# main_board.net
KiCad netlist of a schematic drawn in EAGLE
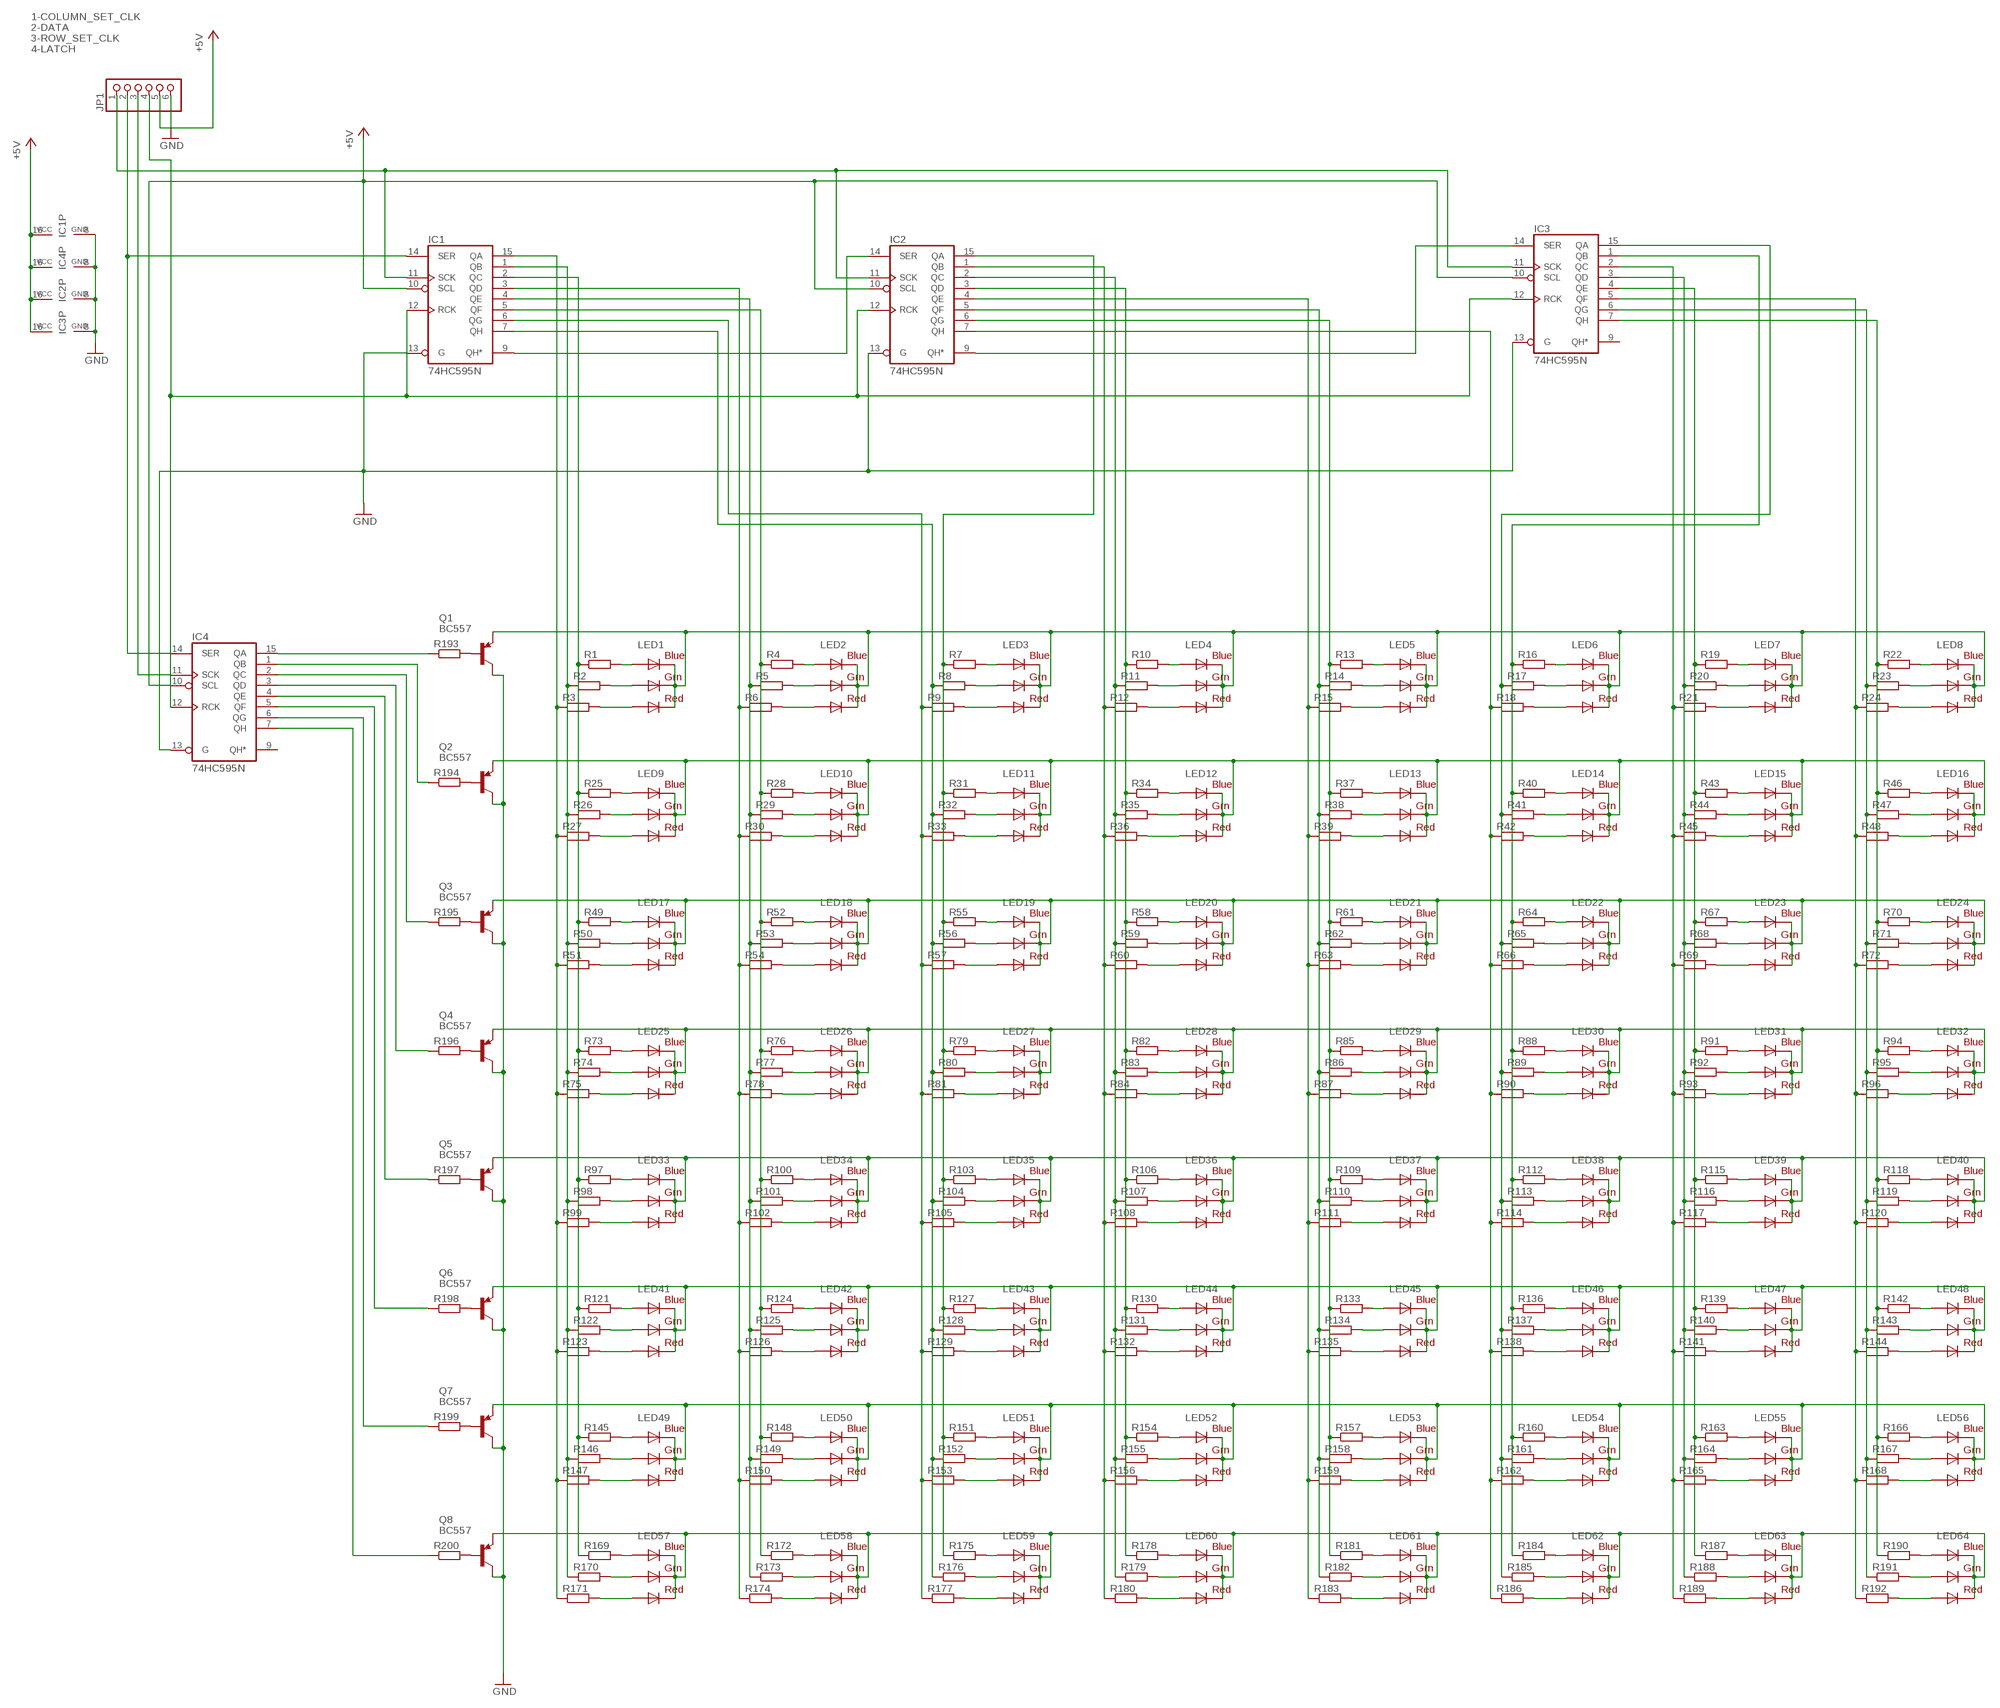
[diagram p0: schematic, sheet 1]

(export (version "E")
  (design (tool "Eeschema 10.0.6"))
  (components
    (comp (ref "IC1")
      (value "74HC595N")
      (footprint "eagle-import:DIL16")
      (libsource (lib "eagle-import") (part "74595NHC"))
    )
    (comp (ref "IC2")
      (value "74HC595N")
      (footprint "eagle-import:DIL16")
      (libsource (lib "eagle-import") (part "74595NHC"))
    )
    (comp (ref "IC3")
      (value "74HC595N")
      (footprint "eagle-import:DIL16")
      (libsource (lib "eagle-import") (part "74595NHC"))
    )
    (comp (ref "IC4")
      (value "74HC595N")
      (footprint "eagle-import:DIL16")
      (libsource (lib "eagle-import") (part "74595NHC"))
    )
    (comp (ref "JP1")
      (value "PINHD-1X6")
      (footprint "eagle-import:1X06")
      (libsource (lib "eagle-import") (part "PINHD-1X6"))
    )
    (comp (ref "LED1")
      (value "RGBLED5050")
      (footprint "eagle-import:RGBLED5050")
      (libsource (lib "eagle-import") (part "RGBLED5050"))
    )
    (comp (ref "LED2")
      (value "RGBLED5050")
      (footprint "eagle-import:RGBLED5050")
      (libsource (lib "eagle-import") (part "RGBLED5050"))
    )
    (comp (ref "LED3")
      (value "RGBLED5050")
      (footprint "eagle-import:RGBLED5050")
      (libsource (lib "eagle-import") (part "RGBLED5050"))
    )
    (comp (ref "LED4")
      (value "RGBLED5050")
      (footprint "eagle-import:RGBLED5050")
      (libsource (lib "eagle-import") (part "RGBLED5050"))
    )
    (comp (ref "LED5")
      (value "RGBLED5050")
      (footprint "eagle-import:RGBLED5050")
      (libsource (lib "eagle-import") (part "RGBLED5050"))
    )
    (comp (ref "LED6")
      (value "RGBLED5050")
      (footprint "eagle-import:RGBLED5050")
      (libsource (lib "eagle-import") (part "RGBLED5050"))
    )
    (comp (ref "LED7")
      (value "RGBLED5050")
      (footprint "eagle-import:RGBLED5050")
      (libsource (lib "eagle-import") (part "RGBLED5050"))
    )
    (comp (ref "LED8")
      (value "RGBLED5050")
      (footprint "eagle-import:RGBLED5050")
      (libsource (lib "eagle-import") (part "RGBLED5050"))
    )
    (comp (ref "LED9")
      (value "RGBLED5050")
      (footprint "eagle-import:RGBLED5050")
      (libsource (lib "eagle-import") (part "RGBLED5050"))
    )
    (comp (ref "LED10")
      (value "RGBLED5050")
      (footprint "eagle-import:RGBLED5050")
      (libsource (lib "eagle-import") (part "RGBLED5050"))
    )
    (comp (ref "LED11")
      (value "RGBLED5050")
      (footprint "eagle-import:RGBLED5050")
      (libsource (lib "eagle-import") (part "RGBLED5050"))
    )
    (comp (ref "LED12")
      (value "RGBLED5050")
      (footprint "eagle-import:RGBLED5050")
      (libsource (lib "eagle-import") (part "RGBLED5050"))
    )
    (comp (ref "LED13")
      (value "RGBLED5050")
      (footprint "eagle-import:RGBLED5050")
      (libsource (lib "eagle-import") (part "RGBLED5050"))
    )
    (comp (ref "LED14")
      (value "RGBLED5050")
      (footprint "eagle-import:RGBLED5050")
      (libsource (lib "eagle-import") (part "RGBLED5050"))
    )
    (comp (ref "LED15")
      (value "RGBLED5050")
      (footprint "eagle-import:RGBLED5050")
      (libsource (lib "eagle-import") (part "RGBLED5050"))
    )
    (comp (ref "LED16")
      (value "RGBLED5050")
      (footprint "eagle-import:RGBLED5050")
      (libsource (lib "eagle-import") (part "RGBLED5050"))
    )
    (comp (ref "LED17")
      (value "RGBLED5050")
      (footprint "eagle-import:RGBLED5050")
      (libsource (lib "eagle-import") (part "RGBLED5050"))
    )
    (comp (ref "LED18")
      (value "RGBLED5050")
      (footprint "eagle-import:RGBLED5050")
      (libsource (lib "eagle-import") (part "RGBLED5050"))
    )
    (comp (ref "LED19")
      (value "RGBLED5050")
      (footprint "eagle-import:RGBLED5050")
      (libsource (lib "eagle-import") (part "RGBLED5050"))
    )
    (comp (ref "LED20")
      (value "RGBLED5050")
      (footprint "eagle-import:RGBLED5050")
      (libsource (lib "eagle-import") (part "RGBLED5050"))
    )
    (comp (ref "LED21")
      (value "RGBLED5050")
      (footprint "eagle-import:RGBLED5050")
      (libsource (lib "eagle-import") (part "RGBLED5050"))
    )
    (comp (ref "LED22")
      (value "RGBLED5050")
      (footprint "eagle-import:RGBLED5050")
      (libsource (lib "eagle-import") (part "RGBLED5050"))
    )
    (comp (ref "LED23")
      (value "RGBLED5050")
      (footprint "eagle-import:RGBLED5050")
      (libsource (lib "eagle-import") (part "RGBLED5050"))
    )
    (comp (ref "LED24")
      (value "RGBLED5050")
      (footprint "eagle-import:RGBLED5050")
      (libsource (lib "eagle-import") (part "RGBLED5050"))
    )
    (comp (ref "LED25")
      (value "RGBLED5050")
      (footprint "eagle-import:RGBLED5050")
      (libsource (lib "eagle-import") (part "RGBLED5050"))
    )
    (comp (ref "LED26")
      (value "RGBLED5050")
      (footprint "eagle-import:RGBLED5050")
      (libsource (lib "eagle-import") (part "RGBLED5050"))
    )
    (comp (ref "LED27")
      (value "RGBLED5050")
      (footprint "eagle-import:RGBLED5050")
      (libsource (lib "eagle-import") (part "RGBLED5050"))
    )
    (comp (ref "LED28")
      (value "RGBLED5050")
      (footprint "eagle-import:RGBLED5050")
      (libsource (lib "eagle-import") (part "RGBLED5050"))
    )
    (comp (ref "LED29")
      (value "RGBLED5050")
      (footprint "eagle-import:RGBLED5050")
      (libsource (lib "eagle-import") (part "RGBLED5050"))
    )
    (comp (ref "LED30")
      (value "RGBLED5050")
      (footprint "eagle-import:RGBLED5050")
      (libsource (lib "eagle-import") (part "RGBLED5050"))
    )
    (comp (ref "LED31")
      (value "RGBLED5050")
      (footprint "eagle-import:RGBLED5050")
      (libsource (lib "eagle-import") (part "RGBLED5050"))
    )
    (comp (ref "LED32")
      (value "RGBLED5050")
      (footprint "eagle-import:RGBLED5050")
      (libsource (lib "eagle-import") (part "RGBLED5050"))
    )
    (comp (ref "LED33")
      (value "RGBLED5050")
      (footprint "eagle-import:RGBLED5050")
      (libsource (lib "eagle-import") (part "RGBLED5050"))
    )
    (comp (ref "LED34")
      (value "RGBLED5050")
      (footprint "eagle-import:RGBLED5050")
      (libsource (lib "eagle-import") (part "RGBLED5050"))
    )
    (comp (ref "LED35")
      (value "RGBLED5050")
      (footprint "eagle-import:RGBLED5050")
      (libsource (lib "eagle-import") (part "RGBLED5050"))
    )
    (comp (ref "LED36")
      (value "RGBLED5050")
      (footprint "eagle-import:RGBLED5050")
      (libsource (lib "eagle-import") (part "RGBLED5050"))
    )
    (comp (ref "LED37")
      (value "RGBLED5050")
      (footprint "eagle-import:RGBLED5050")
      (libsource (lib "eagle-import") (part "RGBLED5050"))
    )
    (comp (ref "LED38")
      (value "RGBLED5050")
      (footprint "eagle-import:RGBLED5050")
      (libsource (lib "eagle-import") (part "RGBLED5050"))
    )
    (comp (ref "LED39")
      (value "RGBLED5050")
      (footprint "eagle-import:RGBLED5050")
      (libsource (lib "eagle-import") (part "RGBLED5050"))
    )
    (comp (ref "LED40")
      (value "RGBLED5050")
      (footprint "eagle-import:RGBLED5050")
      (libsource (lib "eagle-import") (part "RGBLED5050"))
    )
    (comp (ref "LED41")
      (value "RGBLED5050")
      (footprint "eagle-import:RGBLED5050")
      (libsource (lib "eagle-import") (part "RGBLED5050"))
    )
    (comp (ref "LED42")
      (value "RGBLED5050")
      (footprint "eagle-import:RGBLED5050")
      (libsource (lib "eagle-import") (part "RGBLED5050"))
    )
    (comp (ref "LED43")
      (value "RGBLED5050")
      (footprint "eagle-import:RGBLED5050")
      (libsource (lib "eagle-import") (part "RGBLED5050"))
    )
    (comp (ref "LED44")
      (value "RGBLED5050")
      (footprint "eagle-import:RGBLED5050")
      (libsource (lib "eagle-import") (part "RGBLED5050"))
    )
    (comp (ref "LED45")
      (value "RGBLED5050")
      (footprint "eagle-import:RGBLED5050")
      (libsource (lib "eagle-import") (part "RGBLED5050"))
    )
    (comp (ref "LED46")
      (value "RGBLED5050")
      (footprint "eagle-import:RGBLED5050")
      (libsource (lib "eagle-import") (part "RGBLED5050"))
    )
    (comp (ref "LED47")
      (value "RGBLED5050")
      (footprint "eagle-import:RGBLED5050")
      (libsource (lib "eagle-import") (part "RGBLED5050"))
    )
    (comp (ref "LED48")
      (value "RGBLED5050")
      (footprint "eagle-import:RGBLED5050")
      (libsource (lib "eagle-import") (part "RGBLED5050"))
    )
    (comp (ref "LED49")
      (value "RGBLED5050")
      (footprint "eagle-import:RGBLED5050")
      (libsource (lib "eagle-import") (part "RGBLED5050"))
    )
    (comp (ref "LED50")
      (value "RGBLED5050")
      (footprint "eagle-import:RGBLED5050")
      (libsource (lib "eagle-import") (part "RGBLED5050"))
    )
    (comp (ref "LED51")
      (value "RGBLED5050")
      (footprint "eagle-import:RGBLED5050")
      (libsource (lib "eagle-import") (part "RGBLED5050"))
    )
    (comp (ref "LED52")
      (value "RGBLED5050")
      (footprint "eagle-import:RGBLED5050")
      (libsource (lib "eagle-import") (part "RGBLED5050"))
    )
    (comp (ref "LED53")
      (value "RGBLED5050")
      (footprint "eagle-import:RGBLED5050")
      (libsource (lib "eagle-import") (part "RGBLED5050"))
    )
    (comp (ref "LED54")
      (value "RGBLED5050")
      (footprint "eagle-import:RGBLED5050")
      (libsource (lib "eagle-import") (part "RGBLED5050"))
    )
    (comp (ref "LED55")
      (value "RGBLED5050")
      (footprint "eagle-import:RGBLED5050")
      (libsource (lib "eagle-import") (part "RGBLED5050"))
    )
    (comp (ref "LED56")
      (value "RGBLED5050")
      (footprint "eagle-import:RGBLED5050")
      (libsource (lib "eagle-import") (part "RGBLED5050"))
    )
    (comp (ref "LED57")
      (value "RGBLED5050")
      (footprint "eagle-import:RGBLED5050")
      (libsource (lib "eagle-import") (part "RGBLED5050"))
    )
    (comp (ref "LED58")
      (value "RGBLED5050")
      (footprint "eagle-import:RGBLED5050")
      (libsource (lib "eagle-import") (part "RGBLED5050"))
    )
    (comp (ref "LED59")
      (value "RGBLED5050")
      (footprint "eagle-import:RGBLED5050")
      (libsource (lib "eagle-import") (part "RGBLED5050"))
    )
    (comp (ref "LED60")
      (value "RGBLED5050")
      (footprint "eagle-import:RGBLED5050")
      (libsource (lib "eagle-import") (part "RGBLED5050"))
    )
    (comp (ref "LED61")
      (value "RGBLED5050")
      (footprint "eagle-import:RGBLED5050")
      (libsource (lib "eagle-import") (part "RGBLED5050"))
    )
    (comp (ref "LED62")
      (value "RGBLED5050")
      (footprint "eagle-import:RGBLED5050")
      (libsource (lib "eagle-import") (part "RGBLED5050"))
    )
    (comp (ref "LED63")
      (value "RGBLED5050")
      (footprint "eagle-import:RGBLED5050")
      (libsource (lib "eagle-import") (part "RGBLED5050"))
    )
    (comp (ref "LED64")
      (value "RGBLED5050")
      (footprint "eagle-import:RGBLED5050")
      (libsource (lib "eagle-import") (part "RGBLED5050"))
    )
    (comp (ref "Q1")
      (value "BC557")
      (footprint "eagle-import:TO92")
      (libsource (lib "eagle-import") (part "BC557"))
    )
    (comp (ref "Q2")
      (value "BC557")
      (footprint "eagle-import:TO92")
      (libsource (lib "eagle-import") (part "BC557"))
    )
    (comp (ref "Q3")
      (value "BC557")
      (footprint "eagle-import:TO92")
      (libsource (lib "eagle-import") (part "BC557"))
    )
    (comp (ref "Q4")
      (value "BC557")
      (footprint "eagle-import:TO92")
      (libsource (lib "eagle-import") (part "BC557"))
    )
    (comp (ref "Q5")
      (value "BC557")
      (footprint "eagle-import:TO92")
      (libsource (lib "eagle-import") (part "BC557"))
    )
    (comp (ref "Q6")
      (value "BC557")
      (footprint "eagle-import:TO92")
      (libsource (lib "eagle-import") (part "BC557"))
    )
    (comp (ref "Q7")
      (value "BC557")
      (footprint "eagle-import:TO92")
      (libsource (lib "eagle-import") (part "BC557"))
    )
    (comp (ref "Q8")
      (value "BC557")
      (footprint "eagle-import:TO92")
      (libsource (lib "eagle-import") (part "BC557"))
    )
    (comp (ref "R1")
      (value "R-EU_R0805")
      (footprint "eagle-import:R0805")
      (libsource (lib "eagle-import") (part "R-EU_R0805"))
    )
    (comp (ref "R2")
      (value "R-EU_R0805")
      (footprint "eagle-import:R0805")
      (libsource (lib "eagle-import") (part "R-EU_R0805"))
    )
    (comp (ref "R3")
      (value "R-EU_R0805")
      (footprint "eagle-import:R0805")
      (libsource (lib "eagle-import") (part "R-EU_R0805"))
    )
    (comp (ref "R4")
      (value "R-EU_R0805")
      (footprint "eagle-import:R0805")
      (libsource (lib "eagle-import") (part "R-EU_R0805"))
    )
    (comp (ref "R5")
      (value "R-EU_R0805")
      (footprint "eagle-import:R0805")
      (libsource (lib "eagle-import") (part "R-EU_R0805"))
    )
    (comp (ref "R6")
      (value "R-EU_R0805")
      (footprint "eagle-import:R0805")
      (libsource (lib "eagle-import") (part "R-EU_R0805"))
    )
    (comp (ref "R7")
      (value "R-EU_R0805")
      (footprint "eagle-import:R0805")
      (libsource (lib "eagle-import") (part "R-EU_R0805"))
    )
    (comp (ref "R8")
      (value "R-EU_R0805")
      (footprint "eagle-import:R0805")
      (libsource (lib "eagle-import") (part "R-EU_R0805"))
    )
    (comp (ref "R9")
      (value "R-EU_R0805")
      (footprint "eagle-import:R0805")
      (libsource (lib "eagle-import") (part "R-EU_R0805"))
    )
    (comp (ref "R10")
      (value "R-EU_R0805")
      (footprint "eagle-import:R0805")
      (libsource (lib "eagle-import") (part "R-EU_R0805"))
    )
    (comp (ref "R11")
      (value "R-EU_R0805")
      (footprint "eagle-import:R0805")
      (libsource (lib "eagle-import") (part "R-EU_R0805"))
    )
    (comp (ref "R12")
      (value "R-EU_R0805")
      (footprint "eagle-import:R0805")
      (libsource (lib "eagle-import") (part "R-EU_R0805"))
    )
    (comp (ref "R13")
      (value "R-EU_R0805")
      (footprint "eagle-import:R0805")
      (libsource (lib "eagle-import") (part "R-EU_R0805"))
    )
    (comp (ref "R14")
      (value "R-EU_R0805")
      (footprint "eagle-import:R0805")
      (libsource (lib "eagle-import") (part "R-EU_R0805"))
    )
    (comp (ref "R15")
      (value "R-EU_R0805")
      (footprint "eagle-import:R0805")
      (libsource (lib "eagle-import") (part "R-EU_R0805"))
    )
    (comp (ref "R16")
      (value "R-EU_R0805")
      (footprint "eagle-import:R0805")
      (libsource (lib "eagle-import") (part "R-EU_R0805"))
    )
    (comp (ref "R17")
      (value "R-EU_R0805")
      (footprint "eagle-import:R0805")
      (libsource (lib "eagle-import") (part "R-EU_R0805"))
    )
    (comp (ref "R18")
      (value "R-EU_R0805")
      (footprint "eagle-import:R0805")
      (libsource (lib "eagle-import") (part "R-EU_R0805"))
    )
    (comp (ref "R19")
      (value "R-EU_R0805")
      (footprint "eagle-import:R0805")
      (libsource (lib "eagle-import") (part "R-EU_R0805"))
    )
    (comp (ref "R20")
      (value "R-EU_R0805")
      (footprint "eagle-import:R0805")
      (libsource (lib "eagle-import") (part "R-EU_R0805"))
    )
    (comp (ref "R21")
      (value "R-EU_R0805")
      (footprint "eagle-import:R0805")
      (libsource (lib "eagle-import") (part "R-EU_R0805"))
    )
    (comp (ref "R22")
      (value "R-EU_R0805")
      (footprint "eagle-import:R0805")
      (libsource (lib "eagle-import") (part "R-EU_R0805"))
    )
    (comp (ref "R23")
      (value "R-EU_R0805")
      (footprint "eagle-import:R0805")
      (libsource (lib "eagle-import") (part "R-EU_R0805"))
    )
    (comp (ref "R24")
      (value "R-EU_R0805")
      (footprint "eagle-import:R0805")
      (libsource (lib "eagle-import") (part "R-EU_R0805"))
    )
    (comp (ref "R25")
      (value "R-EU_R0805")
      (footprint "eagle-import:R0805")
      (libsource (lib "eagle-import") (part "R-EU_R0805"))
    )
    (comp (ref "R26")
      (value "R-EU_R0805")
      (footprint "eagle-import:R0805")
      (libsource (lib "eagle-import") (part "R-EU_R0805"))
    )
    (comp (ref "R27")
      (value "R-EU_R0805")
      (footprint "eagle-import:R0805")
      (libsource (lib "eagle-import") (part "R-EU_R0805"))
    )
    (comp (ref "R28")
      (value "R-EU_R0805")
      (footprint "eagle-import:R0805")
      (libsource (lib "eagle-import") (part "R-EU_R0805"))
    )
    (comp (ref "R29")
      (value "R-EU_R0805")
      (footprint "eagle-import:R0805")
      (libsource (lib "eagle-import") (part "R-EU_R0805"))
    )
    (comp (ref "R30")
      (value "R-EU_R0805")
      (footprint "eagle-import:R0805")
      (libsource (lib "eagle-import") (part "R-EU_R0805"))
    )
    (comp (ref "R31")
      (value "R-EU_R0805")
      (footprint "eagle-import:R0805")
      (libsource (lib "eagle-import") (part "R-EU_R0805"))
    )
    (comp (ref "R32")
      (value "R-EU_R0805")
      (footprint "eagle-import:R0805")
      (libsource (lib "eagle-import") (part "R-EU_R0805"))
    )
    (comp (ref "R33")
      (value "R-EU_R0805")
      (footprint "eagle-import:R0805")
      (libsource (lib "eagle-import") (part "R-EU_R0805"))
    )
    (comp (ref "R34")
      (value "R-EU_R0805")
      (footprint "eagle-import:R0805")
      (libsource (lib "eagle-import") (part "R-EU_R0805"))
    )
    (comp (ref "R35")
      (value "R-EU_R0805")
      (footprint "eagle-import:R0805")
      (libsource (lib "eagle-import") (part "R-EU_R0805"))
    )
    (comp (ref "R36")
      (value "R-EU_R0805")
      (footprint "eagle-import:R0805")
      (libsource (lib "eagle-import") (part "R-EU_R0805"))
    )
    (comp (ref "R37")
      (value "R-EU_R0805")
      (footprint "eagle-import:R0805")
      (libsource (lib "eagle-import") (part "R-EU_R0805"))
    )
    (comp (ref "R38")
      (value "R-EU_R0805")
      (footprint "eagle-import:R0805")
      (libsource (lib "eagle-import") (part "R-EU_R0805"))
    )
    (comp (ref "R39")
      (value "R-EU_R0805")
      (footprint "eagle-import:R0805")
      (libsource (lib "eagle-import") (part "R-EU_R0805"))
    )
    (comp (ref "R40")
      (value "R-EU_R0805")
      (footprint "eagle-import:R0805")
      (libsource (lib "eagle-import") (part "R-EU_R0805"))
    )
    (comp (ref "R41")
      (value "R-EU_R0805")
      (footprint "eagle-import:R0805")
      (libsource (lib "eagle-import") (part "R-EU_R0805"))
    )
    (comp (ref "R42")
      (value "R-EU_R0805")
      (footprint "eagle-import:R0805")
      (libsource (lib "eagle-import") (part "R-EU_R0805"))
    )
    (comp (ref "R43")
      (value "R-EU_R0805")
      (footprint "eagle-import:R0805")
      (libsource (lib "eagle-import") (part "R-EU_R0805"))
    )
    (comp (ref "R44")
      (value "R-EU_R0805")
      (footprint "eagle-import:R0805")
      (libsource (lib "eagle-import") (part "R-EU_R0805"))
    )
    (comp (ref "R45")
      (value "R-EU_R0805")
      (footprint "eagle-import:R0805")
      (libsource (lib "eagle-import") (part "R-EU_R0805"))
    )
    (comp (ref "R46")
      (value "R-EU_R0805")
      (footprint "eagle-import:R0805")
      (libsource (lib "eagle-import") (part "R-EU_R0805"))
    )
    (comp (ref "R47")
      (value "R-EU_R0805")
      (footprint "eagle-import:R0805")
      (libsource (lib "eagle-import") (part "R-EU_R0805"))
    )
    (comp (ref "R48")
      (value "R-EU_R0805")
      (footprint "eagle-import:R0805")
      (libsource (lib "eagle-import") (part "R-EU_R0805"))
    )
    (comp (ref "R49")
      (value "R-EU_R0805")
      (footprint "eagle-import:R0805")
      (libsource (lib "eagle-import") (part "R-EU_R0805"))
    )
    (comp (ref "R50")
      (value "R-EU_R0805")
      (footprint "eagle-import:R0805")
      (libsource (lib "eagle-import") (part "R-EU_R0805"))
    )
    (comp (ref "R51")
      (value "R-EU_R0805")
      (footprint "eagle-import:R0805")
      (libsource (lib "eagle-import") (part "R-EU_R0805"))
    )
    (comp (ref "R52")
      (value "R-EU_R0805")
      (footprint "eagle-import:R0805")
      (libsource (lib "eagle-import") (part "R-EU_R0805"))
    )
    (comp (ref "R53")
      (value "R-EU_R0805")
      (footprint "eagle-import:R0805")
      (libsource (lib "eagle-import") (part "R-EU_R0805"))
    )
    (comp (ref "R54")
      (value "R-EU_R0805")
      (footprint "eagle-import:R0805")
      (libsource (lib "eagle-import") (part "R-EU_R0805"))
    )
    (comp (ref "R55")
      (value "R-EU_R0805")
      (footprint "eagle-import:R0805")
      (libsource (lib "eagle-import") (part "R-EU_R0805"))
    )
    (comp (ref "R56")
      (value "R-EU_R0805")
      (footprint "eagle-import:R0805")
      (libsource (lib "eagle-import") (part "R-EU_R0805"))
    )
    (comp (ref "R57")
      (value "R-EU_R0805")
      (footprint "eagle-import:R0805")
      (libsource (lib "eagle-import") (part "R-EU_R0805"))
    )
    (comp (ref "R58")
      (value "R-EU_R0805")
      (footprint "eagle-import:R0805")
      (libsource (lib "eagle-import") (part "R-EU_R0805"))
    )
    (comp (ref "R59")
      (value "R-EU_R0805")
      (footprint "eagle-import:R0805")
      (libsource (lib "eagle-import") (part "R-EU_R0805"))
    )
    (comp (ref "R60")
      (value "R-EU_R0805")
      (footprint "eagle-import:R0805")
      (libsource (lib "eagle-import") (part "R-EU_R0805"))
    )
    (comp (ref "R61")
      (value "R-EU_R0805")
      (footprint "eagle-import:R0805")
      (libsource (lib "eagle-import") (part "R-EU_R0805"))
    )
    (comp (ref "R62")
      (value "R-EU_R0805")
      (footprint "eagle-import:R0805")
      (libsource (lib "eagle-import") (part "R-EU_R0805"))
    )
    (comp (ref "R63")
      (value "R-EU_R0805")
      (footprint "eagle-import:R0805")
      (libsource (lib "eagle-import") (part "R-EU_R0805"))
    )
    (comp (ref "R64")
      (value "R-EU_R0805")
      (footprint "eagle-import:R0805")
      (libsource (lib "eagle-import") (part "R-EU_R0805"))
    )
    (comp (ref "R65")
      (value "R-EU_R0805")
      (footprint "eagle-import:R0805")
      (libsource (lib "eagle-import") (part "R-EU_R0805"))
    )
    (comp (ref "R66")
      (value "R-EU_R0805")
      (footprint "eagle-import:R0805")
      (libsource (lib "eagle-import") (part "R-EU_R0805"))
    )
    (comp (ref "R67")
      (value "R-EU_R0805")
      (footprint "eagle-import:R0805")
      (libsource (lib "eagle-import") (part "R-EU_R0805"))
    )
    (comp (ref "R68")
      (value "R-EU_R0805")
      (footprint "eagle-import:R0805")
      (libsource (lib "eagle-import") (part "R-EU_R0805"))
    )
    (comp (ref "R69")
      (value "R-EU_R0805")
      (footprint "eagle-import:R0805")
      (libsource (lib "eagle-import") (part "R-EU_R0805"))
    )
    (comp (ref "R70")
      (value "R-EU_R0805")
      (footprint "eagle-import:R0805")
      (libsource (lib "eagle-import") (part "R-EU_R0805"))
    )
    (comp (ref "R71")
      (value "R-EU_R0805")
      (footprint "eagle-import:R0805")
      (libsource (lib "eagle-import") (part "R-EU_R0805"))
    )
    (comp (ref "R72")
      (value "R-EU_R0805")
      (footprint "eagle-import:R0805")
      (libsource (lib "eagle-import") (part "R-EU_R0805"))
    )
    (comp (ref "R73")
      (value "R-EU_R0805")
      (footprint "eagle-import:R0805")
      (libsource (lib "eagle-import") (part "R-EU_R0805"))
    )
    (comp (ref "R74")
      (value "R-EU_R0805")
      (footprint "eagle-import:R0805")
      (libsource (lib "eagle-import") (part "R-EU_R0805"))
    )
    (comp (ref "R75")
      (value "R-EU_R0805")
      (footprint "eagle-import:R0805")
      (libsource (lib "eagle-import") (part "R-EU_R0805"))
    )
    (comp (ref "R76")
      (value "R-EU_R0805")
      (footprint "eagle-import:R0805")
      (libsource (lib "eagle-import") (part "R-EU_R0805"))
    )
    (comp (ref "R77")
      (value "R-EU_R0805")
      (footprint "eagle-import:R0805")
      (libsource (lib "eagle-import") (part "R-EU_R0805"))
    )
    (comp (ref "R78")
      (value "R-EU_R0805")
      (footprint "eagle-import:R0805")
      (libsource (lib "eagle-import") (part "R-EU_R0805"))
    )
    (comp (ref "R79")
      (value "R-EU_R0805")
      (footprint "eagle-import:R0805")
      (libsource (lib "eagle-import") (part "R-EU_R0805"))
    )
    (comp (ref "R80")
      (value "R-EU_R0805")
      (footprint "eagle-import:R0805")
      (libsource (lib "eagle-import") (part "R-EU_R0805"))
    )
    (comp (ref "R81")
      (value "R-EU_R0805")
      (footprint "eagle-import:R0805")
      (libsource (lib "eagle-import") (part "R-EU_R0805"))
    )
    (comp (ref "R82")
      (value "R-EU_R0805")
      (footprint "eagle-import:R0805")
      (libsource (lib "eagle-import") (part "R-EU_R0805"))
    )
    (comp (ref "R83")
      (value "R-EU_R0805")
      (footprint "eagle-import:R0805")
      (libsource (lib "eagle-import") (part "R-EU_R0805"))
    )
    (comp (ref "R84")
      (value "R-EU_R0805")
      (footprint "eagle-import:R0805")
      (libsource (lib "eagle-import") (part "R-EU_R0805"))
    )
    (comp (ref "R85")
      (value "R-EU_R0805")
      (footprint "eagle-import:R0805")
      (libsource (lib "eagle-import") (part "R-EU_R0805"))
    )
    (comp (ref "R86")
      (value "R-EU_R0805")
      (footprint "eagle-import:R0805")
      (libsource (lib "eagle-import") (part "R-EU_R0805"))
    )
    (comp (ref "R87")
      (value "R-EU_R0805")
      (footprint "eagle-import:R0805")
      (libsource (lib "eagle-import") (part "R-EU_R0805"))
    )
    (comp (ref "R88")
      (value "R-EU_R0805")
      (footprint "eagle-import:R0805")
      (libsource (lib "eagle-import") (part "R-EU_R0805"))
    )
    (comp (ref "R89")
      (value "R-EU_R0805")
      (footprint "eagle-import:R0805")
      (libsource (lib "eagle-import") (part "R-EU_R0805"))
    )
    (comp (ref "R90")
      (value "R-EU_R0805")
      (footprint "eagle-import:R0805")
      (libsource (lib "eagle-import") (part "R-EU_R0805"))
    )
    (comp (ref "R91")
      (value "R-EU_R0805")
      (footprint "eagle-import:R0805")
      (libsource (lib "eagle-import") (part "R-EU_R0805"))
    )
    (comp (ref "R92")
      (value "R-EU_R0805")
      (footprint "eagle-import:R0805")
      (libsource (lib "eagle-import") (part "R-EU_R0805"))
    )
    (comp (ref "R93")
      (value "R-EU_R0805")
      (footprint "eagle-import:R0805")
      (libsource (lib "eagle-import") (part "R-EU_R0805"))
    )
    (comp (ref "R94")
      (value "R-EU_R0805")
      (footprint "eagle-import:R0805")
      (libsource (lib "eagle-import") (part "R-EU_R0805"))
    )
    (comp (ref "R95")
      (value "R-EU_R0805")
      (footprint "eagle-import:R0805")
      (libsource (lib "eagle-import") (part "R-EU_R0805"))
    )
    (comp (ref "R96")
      (value "R-EU_R0805")
      (footprint "eagle-import:R0805")
      (libsource (lib "eagle-import") (part "R-EU_R0805"))
    )
    (comp (ref "R97")
      (value "R-EU_R0805")
      (footprint "eagle-import:R0805")
      (libsource (lib "eagle-import") (part "R-EU_R0805"))
    )
    (comp (ref "R98")
      (value "R-EU_R0805")
      (footprint "eagle-import:R0805")
      (libsource (lib "eagle-import") (part "R-EU_R0805"))
    )
    (comp (ref "R99")
      (value "R-EU_R0805")
      (footprint "eagle-import:R0805")
      (libsource (lib "eagle-import") (part "R-EU_R0805"))
    )
    (comp (ref "R100")
      (value "R-EU_R0805")
      (footprint "eagle-import:R0805")
      (libsource (lib "eagle-import") (part "R-EU_R0805"))
    )
    (comp (ref "R101")
      (value "R-EU_R0805")
      (footprint "eagle-import:R0805")
      (libsource (lib "eagle-import") (part "R-EU_R0805"))
    )
    (comp (ref "R102")
      (value "R-EU_R0805")
      (footprint "eagle-import:R0805")
      (libsource (lib "eagle-import") (part "R-EU_R0805"))
    )
    (comp (ref "R103")
      (value "R-EU_R0805")
      (footprint "eagle-import:R0805")
      (libsource (lib "eagle-import") (part "R-EU_R0805"))
    )
    (comp (ref "R104")
      (value "R-EU_R0805")
      (footprint "eagle-import:R0805")
      (libsource (lib "eagle-import") (part "R-EU_R0805"))
    )
    (comp (ref "R105")
      (value "R-EU_R0805")
      (footprint "eagle-import:R0805")
      (libsource (lib "eagle-import") (part "R-EU_R0805"))
    )
    (comp (ref "R106")
      (value "R-EU_R0805")
      (footprint "eagle-import:R0805")
      (libsource (lib "eagle-import") (part "R-EU_R0805"))
    )
    (comp (ref "R107")
      (value "R-EU_R0805")
      (footprint "eagle-import:R0805")
      (libsource (lib "eagle-import") (part "R-EU_R0805"))
    )
    (comp (ref "R108")
      (value "R-EU_R0805")
      (footprint "eagle-import:R0805")
      (libsource (lib "eagle-import") (part "R-EU_R0805"))
    )
    (comp (ref "R109")
      (value "R-EU_R0805")
      (footprint "eagle-import:R0805")
      (libsource (lib "eagle-import") (part "R-EU_R0805"))
    )
    (comp (ref "R110")
      (value "R-EU_R0805")
      (footprint "eagle-import:R0805")
      (libsource (lib "eagle-import") (part "R-EU_R0805"))
    )
    (comp (ref "R111")
      (value "R-EU_R0805")
      (footprint "eagle-import:R0805")
      (libsource (lib "eagle-import") (part "R-EU_R0805"))
    )
    (comp (ref "R112")
      (value "R-EU_R0805")
      (footprint "eagle-import:R0805")
      (libsource (lib "eagle-import") (part "R-EU_R0805"))
    )
    (comp (ref "R113")
      (value "R-EU_R0805")
      (footprint "eagle-import:R0805")
      (libsource (lib "eagle-import") (part "R-EU_R0805"))
    )
    (comp (ref "R114")
      (value "R-EU_R0805")
      (footprint "eagle-import:R0805")
      (libsource (lib "eagle-import") (part "R-EU_R0805"))
    )
    (comp (ref "R115")
      (value "R-EU_R0805")
      (footprint "eagle-import:R0805")
      (libsource (lib "eagle-import") (part "R-EU_R0805"))
    )
    (comp (ref "R116")
      (value "R-EU_R0805")
      (footprint "eagle-import:R0805")
      (libsource (lib "eagle-import") (part "R-EU_R0805"))
    )
    (comp (ref "R117")
      (value "R-EU_R0805")
      (footprint "eagle-import:R0805")
      (libsource (lib "eagle-import") (part "R-EU_R0805"))
    )
    (comp (ref "R118")
      (value "R-EU_R0805")
      (footprint "eagle-import:R0805")
      (libsource (lib "eagle-import") (part "R-EU_R0805"))
    )
    (comp (ref "R119")
      (value "R-EU_R0805")
      (footprint "eagle-import:R0805")
      (libsource (lib "eagle-import") (part "R-EU_R0805"))
    )
    (comp (ref "R120")
      (value "R-EU_R0805")
      (footprint "eagle-import:R0805")
      (libsource (lib "eagle-import") (part "R-EU_R0805"))
    )
    (comp (ref "R121")
      (value "R-EU_R0805")
      (footprint "eagle-import:R0805")
      (libsource (lib "eagle-import") (part "R-EU_R0805"))
    )
    (comp (ref "R122")
      (value "R-EU_R0805")
      (footprint "eagle-import:R0805")
      (libsource (lib "eagle-import") (part "R-EU_R0805"))
    )
    (comp (ref "R123")
      (value "R-EU_R0805")
      (footprint "eagle-import:R0805")
      (libsource (lib "eagle-import") (part "R-EU_R0805"))
    )
    (comp (ref "R124")
      (value "R-EU_R0805")
      (footprint "eagle-import:R0805")
      (libsource (lib "eagle-import") (part "R-EU_R0805"))
    )
    (comp (ref "R125")
      (value "R-EU_R0805")
      (footprint "eagle-import:R0805")
      (libsource (lib "eagle-import") (part "R-EU_R0805"))
    )
    (comp (ref "R126")
      (value "R-EU_R0805")
      (footprint "eagle-import:R0805")
      (libsource (lib "eagle-import") (part "R-EU_R0805"))
    )
    (comp (ref "R127")
      (value "R-EU_R0805")
      (footprint "eagle-import:R0805")
      (libsource (lib "eagle-import") (part "R-EU_R0805"))
    )
    (comp (ref "R128")
      (value "R-EU_R0805")
      (footprint "eagle-import:R0805")
      (libsource (lib "eagle-import") (part "R-EU_R0805"))
    )
    (comp (ref "R129")
      (value "R-EU_R0805")
      (footprint "eagle-import:R0805")
      (libsource (lib "eagle-import") (part "R-EU_R0805"))
    )
    (comp (ref "R130")
      (value "R-EU_R0805")
      (footprint "eagle-import:R0805")
      (libsource (lib "eagle-import") (part "R-EU_R0805"))
    )
    (comp (ref "R131")
      (value "R-EU_R0805")
      (footprint "eagle-import:R0805")
      (libsource (lib "eagle-import") (part "R-EU_R0805"))
    )
    (comp (ref "R132")
      (value "R-EU_R0805")
      (footprint "eagle-import:R0805")
      (libsource (lib "eagle-import") (part "R-EU_R0805"))
    )
    (comp (ref "R133")
      (value "R-EU_R0805")
      (footprint "eagle-import:R0805")
      (libsource (lib "eagle-import") (part "R-EU_R0805"))
    )
    (comp (ref "R134")
      (value "R-EU_R0805")
      (footprint "eagle-import:R0805")
      (libsource (lib "eagle-import") (part "R-EU_R0805"))
    )
    (comp (ref "R135")
      (value "R-EU_R0805")
      (footprint "eagle-import:R0805")
      (libsource (lib "eagle-import") (part "R-EU_R0805"))
    )
    (comp (ref "R136")
      (value "R-EU_R0805")
      (footprint "eagle-import:R0805")
      (libsource (lib "eagle-import") (part "R-EU_R0805"))
    )
    (comp (ref "R137")
      (value "R-EU_R0805")
      (footprint "eagle-import:R0805")
      (libsource (lib "eagle-import") (part "R-EU_R0805"))
    )
    (comp (ref "R138")
      (value "R-EU_R0805")
      (footprint "eagle-import:R0805")
      (libsource (lib "eagle-import") (part "R-EU_R0805"))
    )
    (comp (ref "R139")
      (value "R-EU_R0805")
      (footprint "eagle-import:R0805")
      (libsource (lib "eagle-import") (part "R-EU_R0805"))
    )
    (comp (ref "R140")
      (value "R-EU_R0805")
      (footprint "eagle-import:R0805")
      (libsource (lib "eagle-import") (part "R-EU_R0805"))
    )
    (comp (ref "R141")
      (value "R-EU_R0805")
      (footprint "eagle-import:R0805")
      (libsource (lib "eagle-import") (part "R-EU_R0805"))
    )
    (comp (ref "R142")
      (value "R-EU_R0805")
      (footprint "eagle-import:R0805")
      (libsource (lib "eagle-import") (part "R-EU_R0805"))
    )
    (comp (ref "R143")
      (value "R-EU_R0805")
      (footprint "eagle-import:R0805")
      (libsource (lib "eagle-import") (part "R-EU_R0805"))
    )
    (comp (ref "R144")
      (value "R-EU_R0805")
      (footprint "eagle-import:R0805")
      (libsource (lib "eagle-import") (part "R-EU_R0805"))
    )
    (comp (ref "R145")
      (value "R-EU_R0805")
      (footprint "eagle-import:R0805")
      (libsource (lib "eagle-import") (part "R-EU_R0805"))
    )
    (comp (ref "R146")
      (value "R-EU_R0805")
      (footprint "eagle-import:R0805")
      (libsource (lib "eagle-import") (part "R-EU_R0805"))
    )
    (comp (ref "R147")
      (value "R-EU_R0805")
      (footprint "eagle-import:R0805")
      (libsource (lib "eagle-import") (part "R-EU_R0805"))
    )
    (comp (ref "R148")
      (value "R-EU_R0805")
      (footprint "eagle-import:R0805")
      (libsource (lib "eagle-import") (part "R-EU_R0805"))
    )
    (comp (ref "R149")
      (value "R-EU_R0805")
      (footprint "eagle-import:R0805")
      (libsource (lib "eagle-import") (part "R-EU_R0805"))
    )
    (comp (ref "R150")
      (value "R-EU_R0805")
      (footprint "eagle-import:R0805")
      (libsource (lib "eagle-import") (part "R-EU_R0805"))
    )
    (comp (ref "R151")
      (value "R-EU_R0805")
      (footprint "eagle-import:R0805")
      (libsource (lib "eagle-import") (part "R-EU_R0805"))
    )
    (comp (ref "R152")
      (value "R-EU_R0805")
      (footprint "eagle-import:R0805")
      (libsource (lib "eagle-import") (part "R-EU_R0805"))
    )
    (comp (ref "R153")
      (value "R-EU_R0805")
      (footprint "eagle-import:R0805")
      (libsource (lib "eagle-import") (part "R-EU_R0805"))
    )
    (comp (ref "R154")
      (value "R-EU_R0805")
      (footprint "eagle-import:R0805")
      (libsource (lib "eagle-import") (part "R-EU_R0805"))
    )
    (comp (ref "R155")
      (value "R-EU_R0805")
      (footprint "eagle-import:R0805")
      (libsource (lib "eagle-import") (part "R-EU_R0805"))
    )
    (comp (ref "R156")
      (value "R-EU_R0805")
      (footprint "eagle-import:R0805")
      (libsource (lib "eagle-import") (part "R-EU_R0805"))
    )
    (comp (ref "R157")
      (value "R-EU_R0805")
      (footprint "eagle-import:R0805")
      (libsource (lib "eagle-import") (part "R-EU_R0805"))
    )
    (comp (ref "R158")
      (value "R-EU_R0805")
      (footprint "eagle-import:R0805")
      (libsource (lib "eagle-import") (part "R-EU_R0805"))
    )
    (comp (ref "R159")
      (value "R-EU_R0805")
      (footprint "eagle-import:R0805")
      (libsource (lib "eagle-import") (part "R-EU_R0805"))
    )
    (comp (ref "R160")
      (value "R-EU_R0805")
      (footprint "eagle-import:R0805")
      (libsource (lib "eagle-import") (part "R-EU_R0805"))
    )
    (comp (ref "R161")
      (value "R-EU_R0805")
      (footprint "eagle-import:R0805")
      (libsource (lib "eagle-import") (part "R-EU_R0805"))
    )
    (comp (ref "R162")
      (value "R-EU_R0805")
      (footprint "eagle-import:R0805")
      (libsource (lib "eagle-import") (part "R-EU_R0805"))
    )
    (comp (ref "R163")
      (value "R-EU_R0805")
      (footprint "eagle-import:R0805")
      (libsource (lib "eagle-import") (part "R-EU_R0805"))
    )
    (comp (ref "R164")
      (value "R-EU_R0805")
      (footprint "eagle-import:R0805")
      (libsource (lib "eagle-import") (part "R-EU_R0805"))
    )
    (comp (ref "R165")
      (value "R-EU_R0805")
      (footprint "eagle-import:R0805")
      (libsource (lib "eagle-import") (part "R-EU_R0805"))
    )
    (comp (ref "R166")
      (value "R-EU_R0805")
      (footprint "eagle-import:R0805")
      (libsource (lib "eagle-import") (part "R-EU_R0805"))
    )
    (comp (ref "R167")
      (value "R-EU_R0805")
      (footprint "eagle-import:R0805")
      (libsource (lib "eagle-import") (part "R-EU_R0805"))
    )
    (comp (ref "R168")
      (value "R-EU_R0805")
      (footprint "eagle-import:R0805")
      (libsource (lib "eagle-import") (part "R-EU_R0805"))
    )
    (comp (ref "R169")
      (value "R-EU_R0805")
      (footprint "eagle-import:R0805")
      (libsource (lib "eagle-import") (part "R-EU_R0805"))
    )
    (comp (ref "R170")
      (value "R-EU_R0805")
      (footprint "eagle-import:R0805")
      (libsource (lib "eagle-import") (part "R-EU_R0805"))
    )
    (comp (ref "R171")
      (value "R-EU_R0805")
      (footprint "eagle-import:R0805")
      (libsource (lib "eagle-import") (part "R-EU_R0805"))
    )
    (comp (ref "R172")
      (value "R-EU_R0805")
      (footprint "eagle-import:R0805")
      (libsource (lib "eagle-import") (part "R-EU_R0805"))
    )
    (comp (ref "R173")
      (value "R-EU_R0805")
      (footprint "eagle-import:R0805")
      (libsource (lib "eagle-import") (part "R-EU_R0805"))
    )
    (comp (ref "R174")
      (value "R-EU_R0805")
      (footprint "eagle-import:R0805")
      (libsource (lib "eagle-import") (part "R-EU_R0805"))
    )
    (comp (ref "R175")
      (value "R-EU_R0805")
      (footprint "eagle-import:R0805")
      (libsource (lib "eagle-import") (part "R-EU_R0805"))
    )
    (comp (ref "R176")
      (value "R-EU_R0805")
      (footprint "eagle-import:R0805")
      (libsource (lib "eagle-import") (part "R-EU_R0805"))
    )
    (comp (ref "R177")
      (value "R-EU_R0805")
      (footprint "eagle-import:R0805")
      (libsource (lib "eagle-import") (part "R-EU_R0805"))
    )
    (comp (ref "R178")
      (value "R-EU_R0805")
      (footprint "eagle-import:R0805")
      (libsource (lib "eagle-import") (part "R-EU_R0805"))
    )
    (comp (ref "R179")
      (value "R-EU_R0805")
      (footprint "eagle-import:R0805")
      (libsource (lib "eagle-import") (part "R-EU_R0805"))
    )
    (comp (ref "R180")
      (value "R-EU_R0805")
      (footprint "eagle-import:R0805")
      (libsource (lib "eagle-import") (part "R-EU_R0805"))
    )
    (comp (ref "R181")
      (value "R-EU_R0805")
      (footprint "eagle-import:R0805")
      (libsource (lib "eagle-import") (part "R-EU_R0805"))
    )
    (comp (ref "R182")
      (value "R-EU_R0805")
      (footprint "eagle-import:R0805")
      (libsource (lib "eagle-import") (part "R-EU_R0805"))
    )
    (comp (ref "R183")
      (value "R-EU_R0805")
      (footprint "eagle-import:R0805")
      (libsource (lib "eagle-import") (part "R-EU_R0805"))
    )
    (comp (ref "R184")
      (value "R-EU_R0805")
      (footprint "eagle-import:R0805")
      (libsource (lib "eagle-import") (part "R-EU_R0805"))
    )
    (comp (ref "R185")
      (value "R-EU_R0805")
      (footprint "eagle-import:R0805")
      (libsource (lib "eagle-import") (part "R-EU_R0805"))
    )
    (comp (ref "R186")
      (value "R-EU_R0805")
      (footprint "eagle-import:R0805")
      (libsource (lib "eagle-import") (part "R-EU_R0805"))
    )
    (comp (ref "R187")
      (value "R-EU_R0805")
      (footprint "eagle-import:R0805")
      (libsource (lib "eagle-import") (part "R-EU_R0805"))
    )
    (comp (ref "R188")
      (value "R-EU_R0805")
      (footprint "eagle-import:R0805")
      (libsource (lib "eagle-import") (part "R-EU_R0805"))
    )
    (comp (ref "R189")
      (value "R-EU_R0805")
      (footprint "eagle-import:R0805")
      (libsource (lib "eagle-import") (part "R-EU_R0805"))
    )
    (comp (ref "R190")
      (value "R-EU_R0805")
      (footprint "eagle-import:R0805")
      (libsource (lib "eagle-import") (part "R-EU_R0805"))
    )
    (comp (ref "R191")
      (value "R-EU_R0805")
      (footprint "eagle-import:R0805")
      (libsource (lib "eagle-import") (part "R-EU_R0805"))
    )
    (comp (ref "R192")
      (value "R-EU_R0805")
      (footprint "eagle-import:R0805")
      (libsource (lib "eagle-import") (part "R-EU_R0805"))
    )
    (comp (ref "R193")
      (value "R-EU_R0805")
      (footprint "eagle-import:R0805")
      (libsource (lib "eagle-import") (part "R-EU_R0805"))
    )
    (comp (ref "R194")
      (value "R-EU_R0805")
      (footprint "eagle-import:R0805")
      (libsource (lib "eagle-import") (part "R-EU_R0805"))
    )
    (comp (ref "R195")
      (value "R-EU_R0805")
      (footprint "eagle-import:R0805")
      (libsource (lib "eagle-import") (part "R-EU_R0805"))
    )
    (comp (ref "R196")
      (value "R-EU_R0805")
      (footprint "eagle-import:R0805")
      (libsource (lib "eagle-import") (part "R-EU_R0805"))
    )
    (comp (ref "R197")
      (value "R-EU_R0805")
      (footprint "eagle-import:R0805")
      (libsource (lib "eagle-import") (part "R-EU_R0805"))
    )
    (comp (ref "R198")
      (value "R-EU_R0805")
      (footprint "eagle-import:R0805")
      (libsource (lib "eagle-import") (part "R-EU_R0805"))
    )
    (comp (ref "R199")
      (value "R-EU_R0805")
      (footprint "eagle-import:R0805")
      (libsource (lib "eagle-import") (part "R-EU_R0805"))
    )
    (comp (ref "R200")
      (value "R-EU_R0805")
      (footprint "eagle-import:R0805")
      (libsource (lib "eagle-import") (part "R-EU_R0805"))
    )
  )
  (nets
    (net (code "1") (name "+5V") (class "Default")
      (node (ref "IC1") (pin "10") (pinfunction "SCL_10") (pintype "input"))
      (node (ref "IC1") (pin "16") (pinfunction "VCC_16") (pintype "power_in"))
      (node (ref "IC2") (pin "10") (pinfunction "SCL_10") (pintype "input"))
      (node (ref "IC2") (pin "16") (pinfunction "VCC_16") (pintype "power_in"))
      (node (ref "IC3") (pin "10") (pinfunction "SCL_10") (pintype "input"))
      (node (ref "IC3") (pin "16") (pinfunction "VCC_16") (pintype "power_in"))
      (node (ref "IC4") (pin "10") (pinfunction "SCL_10") (pintype "input"))
      (node (ref "IC4") (pin "16") (pinfunction "VCC_16") (pintype "power_in"))
      (node (ref "JP1") (pin "5") (pinfunction "5_5") (pintype "passive"))
    )
    (net (code "2") (name "/1-COLUMN_SET_CLK") (class "Default")
      (node (ref "IC1") (pin "11") (pinfunction "SCK_11") (pintype "input"))
      (node (ref "IC2") (pin "11") (pinfunction "SCK_11") (pintype "input"))
      (node (ref "IC3") (pin "11") (pinfunction "SCK_11") (pintype "input"))
      (node (ref "JP1") (pin "1") (pinfunction "1_1") (pintype "passive"))
    )
    (net (code "3") (name "/2-DATA") (class "Default")
      (node (ref "IC1") (pin "14") (pinfunction "SER_14") (pintype "input"))
      (node (ref "IC4") (pin "14") (pinfunction "SER_14") (pintype "input"))
      (node (ref "JP1") (pin "2") (pinfunction "2_2") (pintype "passive"))
    )
    (net (code "4") (name "/3-ROW_SET_CLK") (class "Default")
      (node (ref "IC4") (pin "11") (pinfunction "SCK_11") (pintype "input"))
      (node (ref "JP1") (pin "3") (pinfunction "3_3") (pintype "passive"))
    )
    (net (code "5") (name "/4-LATCH") (class "Default")
      (node (ref "IC1") (pin "12") (pinfunction "RCK_12") (pintype "input"))
      (node (ref "IC2") (pin "12") (pinfunction "RCK_12") (pintype "input"))
      (node (ref "IC3") (pin "12") (pinfunction "RCK_12") (pintype "input"))
      (node (ref "IC4") (pin "12") (pinfunction "RCK_12") (pintype "input"))
      (node (ref "JP1") (pin "4") (pinfunction "4_4") (pintype "passive"))
    )
    (net (code "6") (name "GND") (class "Default")
      (node (ref "IC1") (pin "13") (pinfunction "G_13") (pintype "input"))
      (node (ref "IC1") (pin "8") (pinfunction "GND_8") (pintype "power_in"))
      (node (ref "IC2") (pin "13") (pinfunction "G_13") (pintype "input"))
      (node (ref "IC2") (pin "8") (pinfunction "GND_8") (pintype "power_in"))
      (node (ref "IC3") (pin "13") (pinfunction "G_13") (pintype "input"))
      (node (ref "IC3") (pin "8") (pinfunction "GND_8") (pintype "power_in"))
      (node (ref "IC4") (pin "13") (pinfunction "G_13") (pintype "input"))
      (node (ref "IC4") (pin "8") (pinfunction "GND_8") (pintype "power_in"))
      (node (ref "JP1") (pin "6") (pinfunction "6_6") (pintype "passive"))
      (node (ref "Q1") (pin "3") (pinfunction "C_3") (pintype "passive"))
      (node (ref "Q2") (pin "3") (pinfunction "C_3") (pintype "passive"))
      (node (ref "Q3") (pin "3") (pinfunction "C_3") (pintype "passive"))
      (node (ref "Q4") (pin "3") (pinfunction "C_3") (pintype "passive"))
      (node (ref "Q5") (pin "3") (pinfunction "C_3") (pintype "passive"))
      (node (ref "Q6") (pin "3") (pinfunction "C_3") (pintype "passive"))
      (node (ref "Q7") (pin "3") (pinfunction "C_3") (pintype "passive"))
      (node (ref "Q8") (pin "3") (pinfunction "C_3") (pintype "passive"))
    )
    (net (code "7") (name "Net-(IC1A-QA)") (class "Default")
      (node (ref "IC1") (pin "15") (pinfunction "QA_15") (pintype "tri_state"))
      (node (ref "R123") (pin "1") (pinfunction "1_1") (pintype "passive"))
      (node (ref "R147") (pin "1") (pinfunction "1_1") (pintype "passive"))
      (node (ref "R171") (pin "1") (pinfunction "1_1") (pintype "passive"))
      (node (ref "R27") (pin "1") (pinfunction "1_1") (pintype "passive"))
      (node (ref "R3") (pin "1") (pinfunction "1_1") (pintype "passive"))
      (node (ref "R51") (pin "1") (pinfunction "1_1") (pintype "passive"))
      (node (ref "R75") (pin "1") (pinfunction "1_1") (pintype "passive"))
      (node (ref "R99") (pin "1") (pinfunction "1_1") (pintype "passive"))
    )
    (net (code "8") (name "Net-(IC1A-QB)") (class "Default")
      (node (ref "IC1") (pin "1") (pinfunction "QB_1") (pintype "tri_state"))
      (node (ref "R122") (pin "1") (pinfunction "1_1") (pintype "passive"))
      (node (ref "R146") (pin "1") (pinfunction "1_1") (pintype "passive"))
      (node (ref "R170") (pin "1") (pinfunction "1_1") (pintype "passive"))
      (node (ref "R2") (pin "1") (pinfunction "1_1") (pintype "passive"))
      (node (ref "R26") (pin "1") (pinfunction "1_1") (pintype "passive"))
      (node (ref "R50") (pin "1") (pinfunction "1_1") (pintype "passive"))
      (node (ref "R74") (pin "1") (pinfunction "1_1") (pintype "passive"))
      (node (ref "R98") (pin "1") (pinfunction "1_1") (pintype "passive"))
    )
    (net (code "9") (name "Net-(IC1A-QC)") (class "Default")
      (node (ref "IC1") (pin "2") (pinfunction "QC_2") (pintype "tri_state"))
      (node (ref "R1") (pin "1") (pinfunction "1_1") (pintype "passive"))
      (node (ref "R121") (pin "1") (pinfunction "1_1") (pintype "passive"))
      (node (ref "R145") (pin "1") (pinfunction "1_1") (pintype "passive"))
      (node (ref "R169") (pin "1") (pinfunction "1_1") (pintype "passive"))
      (node (ref "R25") (pin "1") (pinfunction "1_1") (pintype "passive"))
      (node (ref "R49") (pin "1") (pinfunction "1_1") (pintype "passive"))
      (node (ref "R73") (pin "1") (pinfunction "1_1") (pintype "passive"))
      (node (ref "R97") (pin "1") (pinfunction "1_1") (pintype "passive"))
    )
    (net (code "10") (name "Net-(IC1A-QD)") (class "Default")
      (node (ref "IC1") (pin "3") (pinfunction "QD_3") (pintype "tri_state"))
      (node (ref "R102") (pin "1") (pinfunction "1_1") (pintype "passive"))
      (node (ref "R126") (pin "1") (pinfunction "1_1") (pintype "passive"))
      (node (ref "R150") (pin "1") (pinfunction "1_1") (pintype "passive"))
      (node (ref "R174") (pin "1") (pinfunction "1_1") (pintype "passive"))
      (node (ref "R30") (pin "1") (pinfunction "1_1") (pintype "passive"))
      (node (ref "R54") (pin "1") (pinfunction "1_1") (pintype "passive"))
      (node (ref "R6") (pin "1") (pinfunction "1_1") (pintype "passive"))
      (node (ref "R78") (pin "1") (pinfunction "1_1") (pintype "passive"))
    )
    (net (code "11") (name "Net-(IC1A-QE)") (class "Default")
      (node (ref "IC1") (pin "4") (pinfunction "QE_4") (pintype "tri_state"))
      (node (ref "R101") (pin "1") (pinfunction "1_1") (pintype "passive"))
      (node (ref "R125") (pin "1") (pinfunction "1_1") (pintype "passive"))
      (node (ref "R149") (pin "1") (pinfunction "1_1") (pintype "passive"))
      (node (ref "R173") (pin "1") (pinfunction "1_1") (pintype "passive"))
      (node (ref "R29") (pin "1") (pinfunction "1_1") (pintype "passive"))
      (node (ref "R5") (pin "1") (pinfunction "1_1") (pintype "passive"))
      (node (ref "R53") (pin "1") (pinfunction "1_1") (pintype "passive"))
      (node (ref "R77") (pin "1") (pinfunction "1_1") (pintype "passive"))
    )
    (net (code "12") (name "Net-(IC1A-QF)") (class "Default")
      (node (ref "IC1") (pin "5") (pinfunction "QF_5") (pintype "tri_state"))
      (node (ref "R100") (pin "1") (pinfunction "1_1") (pintype "passive"))
      (node (ref "R124") (pin "1") (pinfunction "1_1") (pintype "passive"))
      (node (ref "R148") (pin "1") (pinfunction "1_1") (pintype "passive"))
      (node (ref "R172") (pin "1") (pinfunction "1_1") (pintype "passive"))
      (node (ref "R28") (pin "1") (pinfunction "1_1") (pintype "passive"))
      (node (ref "R4") (pin "1") (pinfunction "1_1") (pintype "passive"))
      (node (ref "R52") (pin "1") (pinfunction "1_1") (pintype "passive"))
      (node (ref "R76") (pin "1") (pinfunction "1_1") (pintype "passive"))
    )
    (net (code "13") (name "Net-(IC1A-QG)") (class "Default")
      (node (ref "IC1") (pin "6") (pinfunction "QG_6") (pintype "tri_state"))
      (node (ref "R105") (pin "1") (pinfunction "1_1") (pintype "passive"))
      (node (ref "R129") (pin "1") (pinfunction "1_1") (pintype "passive"))
      (node (ref "R153") (pin "1") (pinfunction "1_1") (pintype "passive"))
      (node (ref "R177") (pin "1") (pinfunction "1_1") (pintype "passive"))
      (node (ref "R33") (pin "1") (pinfunction "1_1") (pintype "passive"))
      (node (ref "R57") (pin "1") (pinfunction "1_1") (pintype "passive"))
      (node (ref "R81") (pin "1") (pinfunction "1_1") (pintype "passive"))
      (node (ref "R9") (pin "1") (pinfunction "1_1") (pintype "passive"))
    )
    (net (code "14") (name "Net-(IC1A-QH)") (class "Default")
      (node (ref "IC1") (pin "7") (pinfunction "QH_7") (pintype "tri_state"))
      (node (ref "R104") (pin "1") (pinfunction "1_1") (pintype "passive"))
      (node (ref "R128") (pin "1") (pinfunction "1_1") (pintype "passive"))
      (node (ref "R152") (pin "1") (pinfunction "1_1") (pintype "passive"))
      (node (ref "R176") (pin "1") (pinfunction "1_1") (pintype "passive"))
      (node (ref "R32") (pin "1") (pinfunction "1_1") (pintype "passive"))
      (node (ref "R56") (pin "1") (pinfunction "1_1") (pintype "passive"))
      (node (ref "R8") (pin "1") (pinfunction "1_1") (pintype "passive"))
      (node (ref "R80") (pin "1") (pinfunction "1_1") (pintype "passive"))
    )
    (net (code "15") (name "Net-(IC1A-QH*)") (class "Default")
      (node (ref "IC1") (pin "9") (pinfunction "QH*_9") (pintype "tri_state"))
      (node (ref "IC2") (pin "14") (pinfunction "SER_14") (pintype "input"))
    )
    (net (code "16") (name "Net-(IC2A-QA)") (class "Default")
      (node (ref "IC2") (pin "15") (pinfunction "QA_15") (pintype "tri_state"))
      (node (ref "R103") (pin "1") (pinfunction "1_1") (pintype "passive"))
      (node (ref "R127") (pin "1") (pinfunction "1_1") (pintype "passive"))
      (node (ref "R151") (pin "1") (pinfunction "1_1") (pintype "passive"))
      (node (ref "R175") (pin "1") (pinfunction "1_1") (pintype "passive"))
      (node (ref "R31") (pin "1") (pinfunction "1_1") (pintype "passive"))
      (node (ref "R55") (pin "1") (pinfunction "1_1") (pintype "passive"))
      (node (ref "R7") (pin "1") (pinfunction "1_1") (pintype "passive"))
      (node (ref "R79") (pin "1") (pinfunction "1_1") (pintype "passive"))
    )
    (net (code "17") (name "Net-(IC2A-QB)") (class "Default")
      (node (ref "IC2") (pin "1") (pinfunction "QB_1") (pintype "tri_state"))
      (node (ref "R108") (pin "1") (pinfunction "1_1") (pintype "passive"))
      (node (ref "R12") (pin "1") (pinfunction "1_1") (pintype "passive"))
      (node (ref "R132") (pin "1") (pinfunction "1_1") (pintype "passive"))
      (node (ref "R156") (pin "1") (pinfunction "1_1") (pintype "passive"))
      (node (ref "R180") (pin "1") (pinfunction "1_1") (pintype "passive"))
      (node (ref "R36") (pin "1") (pinfunction "1_1") (pintype "passive"))
      (node (ref "R60") (pin "1") (pinfunction "1_1") (pintype "passive"))
      (node (ref "R84") (pin "1") (pinfunction "1_1") (pintype "passive"))
    )
    (net (code "18") (name "Net-(IC2A-QC)") (class "Default")
      (node (ref "IC2") (pin "2") (pinfunction "QC_2") (pintype "tri_state"))
      (node (ref "R107") (pin "1") (pinfunction "1_1") (pintype "passive"))
      (node (ref "R11") (pin "1") (pinfunction "1_1") (pintype "passive"))
      (node (ref "R131") (pin "1") (pinfunction "1_1") (pintype "passive"))
      (node (ref "R155") (pin "1") (pinfunction "1_1") (pintype "passive"))
      (node (ref "R179") (pin "1") (pinfunction "1_1") (pintype "passive"))
      (node (ref "R35") (pin "1") (pinfunction "1_1") (pintype "passive"))
      (node (ref "R59") (pin "1") (pinfunction "1_1") (pintype "passive"))
      (node (ref "R83") (pin "1") (pinfunction "1_1") (pintype "passive"))
    )
    (net (code "19") (name "Net-(IC2A-QD)") (class "Default")
      (node (ref "IC2") (pin "3") (pinfunction "QD_3") (pintype "tri_state"))
      (node (ref "R10") (pin "1") (pinfunction "1_1") (pintype "passive"))
      (node (ref "R106") (pin "1") (pinfunction "1_1") (pintype "passive"))
      (node (ref "R130") (pin "1") (pinfunction "1_1") (pintype "passive"))
      (node (ref "R154") (pin "1") (pinfunction "1_1") (pintype "passive"))
      (node (ref "R178") (pin "1") (pinfunction "1_1") (pintype "passive"))
      (node (ref "R34") (pin "1") (pinfunction "1_1") (pintype "passive"))
      (node (ref "R58") (pin "1") (pinfunction "1_1") (pintype "passive"))
      (node (ref "R82") (pin "1") (pinfunction "1_1") (pintype "passive"))
    )
    (net (code "20") (name "Net-(IC2A-QE)") (class "Default")
      (node (ref "IC2") (pin "4") (pinfunction "QE_4") (pintype "tri_state"))
      (node (ref "R111") (pin "1") (pinfunction "1_1") (pintype "passive"))
      (node (ref "R135") (pin "1") (pinfunction "1_1") (pintype "passive"))
      (node (ref "R15") (pin "1") (pinfunction "1_1") (pintype "passive"))
      (node (ref "R159") (pin "1") (pinfunction "1_1") (pintype "passive"))
      (node (ref "R183") (pin "1") (pinfunction "1_1") (pintype "passive"))
      (node (ref "R39") (pin "1") (pinfunction "1_1") (pintype "passive"))
      (node (ref "R63") (pin "1") (pinfunction "1_1") (pintype "passive"))
      (node (ref "R87") (pin "1") (pinfunction "1_1") (pintype "passive"))
    )
    (net (code "21") (name "Net-(IC2A-QF)") (class "Default")
      (node (ref "IC2") (pin "5") (pinfunction "QF_5") (pintype "tri_state"))
      (node (ref "R110") (pin "1") (pinfunction "1_1") (pintype "passive"))
      (node (ref "R134") (pin "1") (pinfunction "1_1") (pintype "passive"))
      (node (ref "R14") (pin "1") (pinfunction "1_1") (pintype "passive"))
      (node (ref "R158") (pin "1") (pinfunction "1_1") (pintype "passive"))
      (node (ref "R182") (pin "1") (pinfunction "1_1") (pintype "passive"))
      (node (ref "R38") (pin "1") (pinfunction "1_1") (pintype "passive"))
      (node (ref "R62") (pin "1") (pinfunction "1_1") (pintype "passive"))
      (node (ref "R86") (pin "1") (pinfunction "1_1") (pintype "passive"))
    )
    (net (code "22") (name "Net-(IC2A-QG)") (class "Default")
      (node (ref "IC2") (pin "6") (pinfunction "QG_6") (pintype "tri_state"))
      (node (ref "R109") (pin "1") (pinfunction "1_1") (pintype "passive"))
      (node (ref "R13") (pin "1") (pinfunction "1_1") (pintype "passive"))
      (node (ref "R133") (pin "1") (pinfunction "1_1") (pintype "passive"))
      (node (ref "R157") (pin "1") (pinfunction "1_1") (pintype "passive"))
      (node (ref "R181") (pin "1") (pinfunction "1_1") (pintype "passive"))
      (node (ref "R37") (pin "1") (pinfunction "1_1") (pintype "passive"))
      (node (ref "R61") (pin "1") (pinfunction "1_1") (pintype "passive"))
      (node (ref "R85") (pin "1") (pinfunction "1_1") (pintype "passive"))
    )
    (net (code "23") (name "Net-(IC2A-QH)") (class "Default")
      (node (ref "IC2") (pin "7") (pinfunction "QH_7") (pintype "tri_state"))
      (node (ref "R114") (pin "1") (pinfunction "1_1") (pintype "passive"))
      (node (ref "R138") (pin "1") (pinfunction "1_1") (pintype "passive"))
      (node (ref "R162") (pin "1") (pinfunction "1_1") (pintype "passive"))
      (node (ref "R18") (pin "1") (pinfunction "1_1") (pintype "passive"))
      (node (ref "R186") (pin "1") (pinfunction "1_1") (pintype "passive"))
      (node (ref "R42") (pin "1") (pinfunction "1_1") (pintype "passive"))
      (node (ref "R66") (pin "1") (pinfunction "1_1") (pintype "passive"))
      (node (ref "R90") (pin "1") (pinfunction "1_1") (pintype "passive"))
    )
    (net (code "24") (name "Net-(IC2A-QH*)") (class "Default")
      (node (ref "IC2") (pin "9") (pinfunction "QH*_9") (pintype "tri_state"))
      (node (ref "IC3") (pin "14") (pinfunction "SER_14") (pintype "input"))
    )
    (net (code "25") (name "Net-(IC3A-QA)") (class "Default")
      (node (ref "IC3") (pin "15") (pinfunction "QA_15") (pintype "tri_state"))
      (node (ref "R113") (pin "1") (pinfunction "1_1") (pintype "passive"))
      (node (ref "R137") (pin "1") (pinfunction "1_1") (pintype "passive"))
      (node (ref "R161") (pin "1") (pinfunction "1_1") (pintype "passive"))
      (node (ref "R17") (pin "1") (pinfunction "1_1") (pintype "passive"))
      (node (ref "R185") (pin "1") (pinfunction "1_1") (pintype "passive"))
      (node (ref "R41") (pin "1") (pinfunction "1_1") (pintype "passive"))
      (node (ref "R65") (pin "1") (pinfunction "1_1") (pintype "passive"))
      (node (ref "R89") (pin "1") (pinfunction "1_1") (pintype "passive"))
    )
    (net (code "26") (name "Net-(IC3A-QB)") (class "Default")
      (node (ref "IC3") (pin "1") (pinfunction "QB_1") (pintype "tri_state"))
      (node (ref "R112") (pin "1") (pinfunction "1_1") (pintype "passive"))
      (node (ref "R136") (pin "1") (pinfunction "1_1") (pintype "passive"))
      (node (ref "R16") (pin "1") (pinfunction "1_1") (pintype "passive"))
      (node (ref "R160") (pin "1") (pinfunction "1_1") (pintype "passive"))
      (node (ref "R184") (pin "1") (pinfunction "1_1") (pintype "passive"))
      (node (ref "R40") (pin "1") (pinfunction "1_1") (pintype "passive"))
      (node (ref "R64") (pin "1") (pinfunction "1_1") (pintype "passive"))
      (node (ref "R88") (pin "1") (pinfunction "1_1") (pintype "passive"))
    )
    (net (code "27") (name "Net-(IC3A-QC)") (class "Default")
      (node (ref "IC3") (pin "2") (pinfunction "QC_2") (pintype "tri_state"))
      (node (ref "R117") (pin "1") (pinfunction "1_1") (pintype "passive"))
      (node (ref "R141") (pin "1") (pinfunction "1_1") (pintype "passive"))
      (node (ref "R165") (pin "1") (pinfunction "1_1") (pintype "passive"))
      (node (ref "R189") (pin "1") (pinfunction "1_1") (pintype "passive"))
      (node (ref "R21") (pin "1") (pinfunction "1_1") (pintype "passive"))
      (node (ref "R45") (pin "1") (pinfunction "1_1") (pintype "passive"))
      (node (ref "R69") (pin "1") (pinfunction "1_1") (pintype "passive"))
      (node (ref "R93") (pin "1") (pinfunction "1_1") (pintype "passive"))
    )
    (net (code "28") (name "Net-(IC3A-QD)") (class "Default")
      (node (ref "IC3") (pin "3") (pinfunction "QD_3") (pintype "tri_state"))
      (node (ref "R116") (pin "1") (pinfunction "1_1") (pintype "passive"))
      (node (ref "R140") (pin "1") (pinfunction "1_1") (pintype "passive"))
      (node (ref "R164") (pin "1") (pinfunction "1_1") (pintype "passive"))
      (node (ref "R188") (pin "1") (pinfunction "1_1") (pintype "passive"))
      (node (ref "R20") (pin "1") (pinfunction "1_1") (pintype "passive"))
      (node (ref "R44") (pin "1") (pinfunction "1_1") (pintype "passive"))
      (node (ref "R68") (pin "1") (pinfunction "1_1") (pintype "passive"))
      (node (ref "R92") (pin "1") (pinfunction "1_1") (pintype "passive"))
    )
    (net (code "29") (name "Net-(IC3A-QE)") (class "Default")
      (node (ref "IC3") (pin "4") (pinfunction "QE_4") (pintype "tri_state"))
      (node (ref "R115") (pin "1") (pinfunction "1_1") (pintype "passive"))
      (node (ref "R139") (pin "1") (pinfunction "1_1") (pintype "passive"))
      (node (ref "R163") (pin "1") (pinfunction "1_1") (pintype "passive"))
      (node (ref "R187") (pin "1") (pinfunction "1_1") (pintype "passive"))
      (node (ref "R19") (pin "1") (pinfunction "1_1") (pintype "passive"))
      (node (ref "R43") (pin "1") (pinfunction "1_1") (pintype "passive"))
      (node (ref "R67") (pin "1") (pinfunction "1_1") (pintype "passive"))
      (node (ref "R91") (pin "1") (pinfunction "1_1") (pintype "passive"))
    )
    (net (code "30") (name "Net-(IC3A-QF)") (class "Default")
      (node (ref "IC3") (pin "5") (pinfunction "QF_5") (pintype "tri_state"))
      (node (ref "R120") (pin "1") (pinfunction "1_1") (pintype "passive"))
      (node (ref "R144") (pin "1") (pinfunction "1_1") (pintype "passive"))
      (node (ref "R168") (pin "1") (pinfunction "1_1") (pintype "passive"))
      (node (ref "R192") (pin "1") (pinfunction "1_1") (pintype "passive"))
      (node (ref "R24") (pin "1") (pinfunction "1_1") (pintype "passive"))
      (node (ref "R48") (pin "1") (pinfunction "1_1") (pintype "passive"))
      (node (ref "R72") (pin "1") (pinfunction "1_1") (pintype "passive"))
      (node (ref "R96") (pin "1") (pinfunction "1_1") (pintype "passive"))
    )
    (net (code "31") (name "Net-(IC3A-QG)") (class "Default")
      (node (ref "IC3") (pin "6") (pinfunction "QG_6") (pintype "tri_state"))
      (node (ref "R119") (pin "1") (pinfunction "1_1") (pintype "passive"))
      (node (ref "R143") (pin "1") (pinfunction "1_1") (pintype "passive"))
      (node (ref "R167") (pin "1") (pinfunction "1_1") (pintype "passive"))
      (node (ref "R191") (pin "1") (pinfunction "1_1") (pintype "passive"))
      (node (ref "R23") (pin "1") (pinfunction "1_1") (pintype "passive"))
      (node (ref "R47") (pin "1") (pinfunction "1_1") (pintype "passive"))
      (node (ref "R71") (pin "1") (pinfunction "1_1") (pintype "passive"))
      (node (ref "R95") (pin "1") (pinfunction "1_1") (pintype "passive"))
    )
    (net (code "32") (name "Net-(IC3A-QH)") (class "Default")
      (node (ref "IC3") (pin "7") (pinfunction "QH_7") (pintype "tri_state"))
      (node (ref "R118") (pin "1") (pinfunction "1_1") (pintype "passive"))
      (node (ref "R142") (pin "1") (pinfunction "1_1") (pintype "passive"))
      (node (ref "R166") (pin "1") (pinfunction "1_1") (pintype "passive"))
      (node (ref "R190") (pin "1") (pinfunction "1_1") (pintype "passive"))
      (node (ref "R22") (pin "1") (pinfunction "1_1") (pintype "passive"))
      (node (ref "R46") (pin "1") (pinfunction "1_1") (pintype "passive"))
      (node (ref "R70") (pin "1") (pinfunction "1_1") (pintype "passive"))
      (node (ref "R94") (pin "1") (pinfunction "1_1") (pintype "passive"))
    )
    (net (code "33") (name "Net-(IC4A-QA)") (class "Default")
      (node (ref "IC4") (pin "15") (pinfunction "QA_15") (pintype "tri_state"))
      (node (ref "R193") (pin "1") (pinfunction "1_1") (pintype "passive"))
    )
    (net (code "34") (name "Net-(IC4A-QB)") (class "Default")
      (node (ref "IC4") (pin "1") (pinfunction "QB_1") (pintype "tri_state"))
      (node (ref "R194") (pin "1") (pinfunction "1_1") (pintype "passive"))
    )
    (net (code "35") (name "Net-(IC4A-QC)") (class "Default")
      (node (ref "IC4") (pin "2") (pinfunction "QC_2") (pintype "tri_state"))
      (node (ref "R195") (pin "1") (pinfunction "1_1") (pintype "passive"))
    )
    (net (code "36") (name "Net-(IC4A-QD)") (class "Default")
      (node (ref "IC4") (pin "3") (pinfunction "QD_3") (pintype "tri_state"))
      (node (ref "R196") (pin "1") (pinfunction "1_1") (pintype "passive"))
    )
    (net (code "37") (name "Net-(IC4A-QE)") (class "Default")
      (node (ref "IC4") (pin "4") (pinfunction "QE_4") (pintype "tri_state"))
      (node (ref "R197") (pin "1") (pinfunction "1_1") (pintype "passive"))
    )
    (net (code "38") (name "Net-(IC4A-QF)") (class "Default")
      (node (ref "IC4") (pin "5") (pinfunction "QF_5") (pintype "tri_state"))
      (node (ref "R198") (pin "1") (pinfunction "1_1") (pintype "passive"))
    )
    (net (code "39") (name "Net-(IC4A-QG)") (class "Default")
      (node (ref "IC4") (pin "6") (pinfunction "QG_6") (pintype "tri_state"))
      (node (ref "R199") (pin "1") (pinfunction "1_1") (pintype "passive"))
    )
    (net (code "40") (name "Net-(IC4A-QH)") (class "Default")
      (node (ref "IC4") (pin "7") (pinfunction "QH_7") (pintype "tri_state"))
      (node (ref "R200") (pin "1") (pinfunction "1_1") (pintype "passive"))
    )
    (net (code "41") (name "Net-(LED1-BLUE_A)") (class "Default")
      (node (ref "LED1") (pin "3") (pinfunction "BLUE_A_3") (pintype "bidirectional"))
      (node (ref "R1") (pin "2") (pinfunction "2_2") (pintype "passive"))
    )
    (net (code "42") (name "Net-(LED1-BLUE_C)") (class "Default")
      (node (ref "LED1") (pin "4") (pinfunction "BLUE_C_4") (pintype "bidirectional"))
      (node (ref "LED1") (pin "5") (pinfunction "RED_C_5") (pintype "bidirectional"))
      (node (ref "LED1") (pin "6") (pinfunction "GREEN_C_6") (pintype "bidirectional"))
      (node (ref "LED2") (pin "4") (pinfunction "BLUE_C_4") (pintype "bidirectional"))
      (node (ref "LED2") (pin "5") (pinfunction "RED_C_5") (pintype "bidirectional"))
      (node (ref "LED2") (pin "6") (pinfunction "GREEN_C_6") (pintype "bidirectional"))
      (node (ref "LED3") (pin "4") (pinfunction "BLUE_C_4") (pintype "bidirectional"))
      (node (ref "LED3") (pin "5") (pinfunction "RED_C_5") (pintype "bidirectional"))
      (node (ref "LED3") (pin "6") (pinfunction "GREEN_C_6") (pintype "bidirectional"))
      (node (ref "LED4") (pin "4") (pinfunction "BLUE_C_4") (pintype "bidirectional"))
      (node (ref "LED4") (pin "5") (pinfunction "RED_C_5") (pintype "bidirectional"))
      (node (ref "LED4") (pin "6") (pinfunction "GREEN_C_6") (pintype "bidirectional"))
      (node (ref "LED5") (pin "4") (pinfunction "BLUE_C_4") (pintype "bidirectional"))
      (node (ref "LED5") (pin "5") (pinfunction "RED_C_5") (pintype "bidirectional"))
      (node (ref "LED5") (pin "6") (pinfunction "GREEN_C_6") (pintype "bidirectional"))
      (node (ref "LED6") (pin "4") (pinfunction "BLUE_C_4") (pintype "bidirectional"))
      (node (ref "LED6") (pin "5") (pinfunction "RED_C_5") (pintype "bidirectional"))
      (node (ref "LED6") (pin "6") (pinfunction "GREEN_C_6") (pintype "bidirectional"))
      (node (ref "LED7") (pin "4") (pinfunction "BLUE_C_4") (pintype "bidirectional"))
      (node (ref "LED7") (pin "5") (pinfunction "RED_C_5") (pintype "bidirectional"))
      (node (ref "LED7") (pin "6") (pinfunction "GREEN_C_6") (pintype "bidirectional"))
      (node (ref "LED8") (pin "4") (pinfunction "BLUE_C_4") (pintype "bidirectional"))
      (node (ref "LED8") (pin "5") (pinfunction "RED_C_5") (pintype "bidirectional"))
      (node (ref "LED8") (pin "6") (pinfunction "GREEN_C_6") (pintype "bidirectional"))
      (node (ref "Q1") (pin "1") (pinfunction "E_1") (pintype "passive"))
    )
    (net (code "43") (name "Net-(LED1-GREEN_A)") (class "Default")
      (node (ref "LED1") (pin "1") (pinfunction "GREEN_A_1") (pintype "bidirectional"))
      (node (ref "R2") (pin "2") (pinfunction "2_2") (pintype "passive"))
    )
    (net (code "44") (name "Net-(LED1-RED_A)") (class "Default")
      (node (ref "LED1") (pin "2") (pinfunction "RED_A_2") (pintype "bidirectional"))
      (node (ref "R3") (pin "2") (pinfunction "2_2") (pintype "passive"))
    )
    (net (code "45") (name "Net-(LED2-BLUE_A)") (class "Default")
      (node (ref "LED2") (pin "3") (pinfunction "BLUE_A_3") (pintype "bidirectional"))
      (node (ref "R4") (pin "2") (pinfunction "2_2") (pintype "passive"))
    )
    (net (code "46") (name "Net-(LED2-GREEN_A)") (class "Default")
      (node (ref "LED2") (pin "1") (pinfunction "GREEN_A_1") (pintype "bidirectional"))
      (node (ref "R5") (pin "2") (pinfunction "2_2") (pintype "passive"))
    )
    (net (code "47") (name "Net-(LED2-RED_A)") (class "Default")
      (node (ref "LED2") (pin "2") (pinfunction "RED_A_2") (pintype "bidirectional"))
      (node (ref "R6") (pin "2") (pinfunction "2_2") (pintype "passive"))
    )
    (net (code "48") (name "Net-(LED3-BLUE_A)") (class "Default")
      (node (ref "LED3") (pin "3") (pinfunction "BLUE_A_3") (pintype "bidirectional"))
      (node (ref "R7") (pin "2") (pinfunction "2_2") (pintype "passive"))
    )
    (net (code "49") (name "Net-(LED3-GREEN_A)") (class "Default")
      (node (ref "LED3") (pin "1") (pinfunction "GREEN_A_1") (pintype "bidirectional"))
      (node (ref "R8") (pin "2") (pinfunction "2_2") (pintype "passive"))
    )
    (net (code "50") (name "Net-(LED3-RED_A)") (class "Default")
      (node (ref "LED3") (pin "2") (pinfunction "RED_A_2") (pintype "bidirectional"))
      (node (ref "R9") (pin "2") (pinfunction "2_2") (pintype "passive"))
    )
    (net (code "51") (name "Net-(LED4-BLUE_A)") (class "Default")
      (node (ref "LED4") (pin "3") (pinfunction "BLUE_A_3") (pintype "bidirectional"))
      (node (ref "R10") (pin "2") (pinfunction "2_2") (pintype "passive"))
    )
    (net (code "52") (name "Net-(LED4-GREEN_A)") (class "Default")
      (node (ref "LED4") (pin "1") (pinfunction "GREEN_A_1") (pintype "bidirectional"))
      (node (ref "R11") (pin "2") (pinfunction "2_2") (pintype "passive"))
    )
    (net (code "53") (name "Net-(LED4-RED_A)") (class "Default")
      (node (ref "LED4") (pin "2") (pinfunction "RED_A_2") (pintype "bidirectional"))
      (node (ref "R12") (pin "2") (pinfunction "2_2") (pintype "passive"))
    )
    (net (code "54") (name "Net-(LED5-BLUE_A)") (class "Default")
      (node (ref "LED5") (pin "3") (pinfunction "BLUE_A_3") (pintype "bidirectional"))
      (node (ref "R13") (pin "2") (pinfunction "2_2") (pintype "passive"))
    )
    (net (code "55") (name "Net-(LED5-GREEN_A)") (class "Default")
      (node (ref "LED5") (pin "1") (pinfunction "GREEN_A_1") (pintype "bidirectional"))
      (node (ref "R14") (pin "2") (pinfunction "2_2") (pintype "passive"))
    )
    (net (code "56") (name "Net-(LED5-RED_A)") (class "Default")
      (node (ref "LED5") (pin "2") (pinfunction "RED_A_2") (pintype "bidirectional"))
      (node (ref "R15") (pin "2") (pinfunction "2_2") (pintype "passive"))
    )
    (net (code "57") (name "Net-(LED6-BLUE_A)") (class "Default")
      (node (ref "LED6") (pin "3") (pinfunction "BLUE_A_3") (pintype "bidirectional"))
      (node (ref "R16") (pin "2") (pinfunction "2_2") (pintype "passive"))
    )
    (net (code "58") (name "Net-(LED6-GREEN_A)") (class "Default")
      (node (ref "LED6") (pin "1") (pinfunction "GREEN_A_1") (pintype "bidirectional"))
      (node (ref "R17") (pin "2") (pinfunction "2_2") (pintype "passive"))
    )
    (net (code "59") (name "Net-(LED6-RED_A)") (class "Default")
      (node (ref "LED6") (pin "2") (pinfunction "RED_A_2") (pintype "bidirectional"))
      (node (ref "R18") (pin "2") (pinfunction "2_2") (pintype "passive"))
    )
    (net (code "60") (name "Net-(LED7-BLUE_A)") (class "Default")
      (node (ref "LED7") (pin "3") (pinfunction "BLUE_A_3") (pintype "bidirectional"))
      (node (ref "R19") (pin "2") (pinfunction "2_2") (pintype "passive"))
    )
    (net (code "61") (name "Net-(LED7-GREEN_A)") (class "Default")
      (node (ref "LED7") (pin "1") (pinfunction "GREEN_A_1") (pintype "bidirectional"))
      (node (ref "R20") (pin "2") (pinfunction "2_2") (pintype "passive"))
    )
    (net (code "62") (name "Net-(LED7-RED_A)") (class "Default")
      (node (ref "LED7") (pin "2") (pinfunction "RED_A_2") (pintype "bidirectional"))
      (node (ref "R21") (pin "2") (pinfunction "2_2") (pintype "passive"))
    )
    (net (code "63") (name "Net-(LED8-BLUE_A)") (class "Default")
      (node (ref "LED8") (pin "3") (pinfunction "BLUE_A_3") (pintype "bidirectional"))
      (node (ref "R22") (pin "2") (pinfunction "2_2") (pintype "passive"))
    )
    (net (code "64") (name "Net-(LED8-GREEN_A)") (class "Default")
      (node (ref "LED8") (pin "1") (pinfunction "GREEN_A_1") (pintype "bidirectional"))
      (node (ref "R23") (pin "2") (pinfunction "2_2") (pintype "passive"))
    )
    (net (code "65") (name "Net-(LED8-RED_A)") (class "Default")
      (node (ref "LED8") (pin "2") (pinfunction "RED_A_2") (pintype "bidirectional"))
      (node (ref "R24") (pin "2") (pinfunction "2_2") (pintype "passive"))
    )
    (net (code "66") (name "Net-(LED9-BLUE_A)") (class "Default")
      (node (ref "LED9") (pin "3") (pinfunction "BLUE_A_3") (pintype "bidirectional"))
      (node (ref "R25") (pin "2") (pinfunction "2_2") (pintype "passive"))
    )
    (net (code "67") (name "Net-(LED9-GREEN_A)") (class "Default")
      (node (ref "LED9") (pin "1") (pinfunction "GREEN_A_1") (pintype "bidirectional"))
      (node (ref "R26") (pin "2") (pinfunction "2_2") (pintype "passive"))
    )
    (net (code "68") (name "Net-(LED9-RED_A)") (class "Default")
      (node (ref "LED9") (pin "2") (pinfunction "RED_A_2") (pintype "bidirectional"))
      (node (ref "R27") (pin "2") (pinfunction "2_2") (pintype "passive"))
    )
    (net (code "69") (name "Net-(LED10-BLUE_A)") (class "Default")
      (node (ref "LED10") (pin "3") (pinfunction "BLUE_A_3") (pintype "bidirectional"))
      (node (ref "R28") (pin "2") (pinfunction "2_2") (pintype "passive"))
    )
    (net (code "70") (name "Net-(LED10-BLUE_C)") (class "Default")
      (node (ref "LED10") (pin "4") (pinfunction "BLUE_C_4") (pintype "bidirectional"))
      (node (ref "LED10") (pin "5") (pinfunction "RED_C_5") (pintype "bidirectional"))
      (node (ref "LED10") (pin "6") (pinfunction "GREEN_C_6") (pintype "bidirectional"))
      (node (ref "LED11") (pin "4") (pinfunction "BLUE_C_4") (pintype "bidirectional"))
      (node (ref "LED11") (pin "5") (pinfunction "RED_C_5") (pintype "bidirectional"))
      (node (ref "LED11") (pin "6") (pinfunction "GREEN_C_6") (pintype "bidirectional"))
      (node (ref "LED12") (pin "4") (pinfunction "BLUE_C_4") (pintype "bidirectional"))
      (node (ref "LED12") (pin "5") (pinfunction "RED_C_5") (pintype "bidirectional"))
      (node (ref "LED12") (pin "6") (pinfunction "GREEN_C_6") (pintype "bidirectional"))
      (node (ref "LED13") (pin "4") (pinfunction "BLUE_C_4") (pintype "bidirectional"))
      (node (ref "LED13") (pin "5") (pinfunction "RED_C_5") (pintype "bidirectional"))
      (node (ref "LED13") (pin "6") (pinfunction "GREEN_C_6") (pintype "bidirectional"))
      (node (ref "LED14") (pin "4") (pinfunction "BLUE_C_4") (pintype "bidirectional"))
      (node (ref "LED14") (pin "5") (pinfunction "RED_C_5") (pintype "bidirectional"))
      (node (ref "LED14") (pin "6") (pinfunction "GREEN_C_6") (pintype "bidirectional"))
      (node (ref "LED15") (pin "4") (pinfunction "BLUE_C_4") (pintype "bidirectional"))
      (node (ref "LED15") (pin "5") (pinfunction "RED_C_5") (pintype "bidirectional"))
      (node (ref "LED15") (pin "6") (pinfunction "GREEN_C_6") (pintype "bidirectional"))
      (node (ref "LED16") (pin "4") (pinfunction "BLUE_C_4") (pintype "bidirectional"))
      (node (ref "LED16") (pin "5") (pinfunction "RED_C_5") (pintype "bidirectional"))
      (node (ref "LED16") (pin "6") (pinfunction "GREEN_C_6") (pintype "bidirectional"))
      (node (ref "LED9") (pin "4") (pinfunction "BLUE_C_4") (pintype "bidirectional"))
      (node (ref "LED9") (pin "5") (pinfunction "RED_C_5") (pintype "bidirectional"))
      (node (ref "LED9") (pin "6") (pinfunction "GREEN_C_6") (pintype "bidirectional"))
      (node (ref "Q2") (pin "1") (pinfunction "E_1") (pintype "passive"))
    )
    (net (code "71") (name "Net-(LED10-GREEN_A)") (class "Default")
      (node (ref "LED10") (pin "1") (pinfunction "GREEN_A_1") (pintype "bidirectional"))
      (node (ref "R29") (pin "2") (pinfunction "2_2") (pintype "passive"))
    )
    (net (code "72") (name "Net-(LED10-RED_A)") (class "Default")
      (node (ref "LED10") (pin "2") (pinfunction "RED_A_2") (pintype "bidirectional"))
      (node (ref "R30") (pin "2") (pinfunction "2_2") (pintype "passive"))
    )
    (net (code "73") (name "Net-(LED11-BLUE_A)") (class "Default")
      (node (ref "LED11") (pin "3") (pinfunction "BLUE_A_3") (pintype "bidirectional"))
      (node (ref "R31") (pin "2") (pinfunction "2_2") (pintype "passive"))
    )
    (net (code "74") (name "Net-(LED11-GREEN_A)") (class "Default")
      (node (ref "LED11") (pin "1") (pinfunction "GREEN_A_1") (pintype "bidirectional"))
      (node (ref "R32") (pin "2") (pinfunction "2_2") (pintype "passive"))
    )
    (net (code "75") (name "Net-(LED11-RED_A)") (class "Default")
      (node (ref "LED11") (pin "2") (pinfunction "RED_A_2") (pintype "bidirectional"))
      (node (ref "R33") (pin "2") (pinfunction "2_2") (pintype "passive"))
    )
    (net (code "76") (name "Net-(LED12-BLUE_A)") (class "Default")
      (node (ref "LED12") (pin "3") (pinfunction "BLUE_A_3") (pintype "bidirectional"))
      (node (ref "R34") (pin "2") (pinfunction "2_2") (pintype "passive"))
    )
    (net (code "77") (name "Net-(LED12-GREEN_A)") (class "Default")
      (node (ref "LED12") (pin "1") (pinfunction "GREEN_A_1") (pintype "bidirectional"))
      (node (ref "R35") (pin "2") (pinfunction "2_2") (pintype "passive"))
    )
    (net (code "78") (name "Net-(LED12-RED_A)") (class "Default")
      (node (ref "LED12") (pin "2") (pinfunction "RED_A_2") (pintype "bidirectional"))
      (node (ref "R36") (pin "2") (pinfunction "2_2") (pintype "passive"))
    )
    (net (code "79") (name "Net-(LED13-BLUE_A)") (class "Default")
      (node (ref "LED13") (pin "3") (pinfunction "BLUE_A_3") (pintype "bidirectional"))
      (node (ref "R37") (pin "2") (pinfunction "2_2") (pintype "passive"))
    )
    (net (code "80") (name "Net-(LED13-GREEN_A)") (class "Default")
      (node (ref "LED13") (pin "1") (pinfunction "GREEN_A_1") (pintype "bidirectional"))
      (node (ref "R38") (pin "2") (pinfunction "2_2") (pintype "passive"))
    )
    (net (code "81") (name "Net-(LED13-RED_A)") (class "Default")
      (node (ref "LED13") (pin "2") (pinfunction "RED_A_2") (pintype "bidirectional"))
      (node (ref "R39") (pin "2") (pinfunction "2_2") (pintype "passive"))
    )
    (net (code "82") (name "Net-(LED14-BLUE_A)") (class "Default")
      (node (ref "LED14") (pin "3") (pinfunction "BLUE_A_3") (pintype "bidirectional"))
      (node (ref "R40") (pin "2") (pinfunction "2_2") (pintype "passive"))
    )
    (net (code "83") (name "Net-(LED14-GREEN_A)") (class "Default")
      (node (ref "LED14") (pin "1") (pinfunction "GREEN_A_1") (pintype "bidirectional"))
      (node (ref "R41") (pin "2") (pinfunction "2_2") (pintype "passive"))
    )
    (net (code "84") (name "Net-(LED14-RED_A)") (class "Default")
      (node (ref "LED14") (pin "2") (pinfunction "RED_A_2") (pintype "bidirectional"))
      (node (ref "R42") (pin "2") (pinfunction "2_2") (pintype "passive"))
    )
    (net (code "85") (name "Net-(LED15-BLUE_A)") (class "Default")
      (node (ref "LED15") (pin "3") (pinfunction "BLUE_A_3") (pintype "bidirectional"))
      (node (ref "R43") (pin "2") (pinfunction "2_2") (pintype "passive"))
    )
    (net (code "86") (name "Net-(LED15-GREEN_A)") (class "Default")
      (node (ref "LED15") (pin "1") (pinfunction "GREEN_A_1") (pintype "bidirectional"))
      (node (ref "R44") (pin "2") (pinfunction "2_2") (pintype "passive"))
    )
    (net (code "87") (name "Net-(LED15-RED_A)") (class "Default")
      (node (ref "LED15") (pin "2") (pinfunction "RED_A_2") (pintype "bidirectional"))
      (node (ref "R45") (pin "2") (pinfunction "2_2") (pintype "passive"))
    )
    (net (code "88") (name "Net-(LED16-BLUE_A)") (class "Default")
      (node (ref "LED16") (pin "3") (pinfunction "BLUE_A_3") (pintype "bidirectional"))
      (node (ref "R46") (pin "2") (pinfunction "2_2") (pintype "passive"))
    )
    (net (code "89") (name "Net-(LED16-GREEN_A)") (class "Default")
      (node (ref "LED16") (pin "1") (pinfunction "GREEN_A_1") (pintype "bidirectional"))
      (node (ref "R47") (pin "2") (pinfunction "2_2") (pintype "passive"))
    )
    (net (code "90") (name "Net-(LED16-RED_A)") (class "Default")
      (node (ref "LED16") (pin "2") (pinfunction "RED_A_2") (pintype "bidirectional"))
      (node (ref "R48") (pin "2") (pinfunction "2_2") (pintype "passive"))
    )
    (net (code "91") (name "Net-(LED17-BLUE_A)") (class "Default")
      (node (ref "LED17") (pin "3") (pinfunction "BLUE_A_3") (pintype "bidirectional"))
      (node (ref "R49") (pin "2") (pinfunction "2_2") (pintype "passive"))
    )
    (net (code "92") (name "Net-(LED17-BLUE_C)") (class "Default")
      (node (ref "LED17") (pin "4") (pinfunction "BLUE_C_4") (pintype "bidirectional"))
      (node (ref "LED17") (pin "5") (pinfunction "RED_C_5") (pintype "bidirectional"))
      (node (ref "LED17") (pin "6") (pinfunction "GREEN_C_6") (pintype "bidirectional"))
      (node (ref "LED18") (pin "4") (pinfunction "BLUE_C_4") (pintype "bidirectional"))
      (node (ref "LED18") (pin "5") (pinfunction "RED_C_5") (pintype "bidirectional"))
      (node (ref "LED18") (pin "6") (pinfunction "GREEN_C_6") (pintype "bidirectional"))
      (node (ref "LED19") (pin "4") (pinfunction "BLUE_C_4") (pintype "bidirectional"))
      (node (ref "LED19") (pin "5") (pinfunction "RED_C_5") (pintype "bidirectional"))
      (node (ref "LED19") (pin "6") (pinfunction "GREEN_C_6") (pintype "bidirectional"))
      (node (ref "LED20") (pin "4") (pinfunction "BLUE_C_4") (pintype "bidirectional"))
      (node (ref "LED20") (pin "5") (pinfunction "RED_C_5") (pintype "bidirectional"))
      (node (ref "LED20") (pin "6") (pinfunction "GREEN_C_6") (pintype "bidirectional"))
      (node (ref "LED21") (pin "4") (pinfunction "BLUE_C_4") (pintype "bidirectional"))
      (node (ref "LED21") (pin "5") (pinfunction "RED_C_5") (pintype "bidirectional"))
      (node (ref "LED21") (pin "6") (pinfunction "GREEN_C_6") (pintype "bidirectional"))
      (node (ref "LED22") (pin "4") (pinfunction "BLUE_C_4") (pintype "bidirectional"))
      (node (ref "LED22") (pin "5") (pinfunction "RED_C_5") (pintype "bidirectional"))
      (node (ref "LED22") (pin "6") (pinfunction "GREEN_C_6") (pintype "bidirectional"))
      (node (ref "LED23") (pin "4") (pinfunction "BLUE_C_4") (pintype "bidirectional"))
      (node (ref "LED23") (pin "5") (pinfunction "RED_C_5") (pintype "bidirectional"))
      (node (ref "LED23") (pin "6") (pinfunction "GREEN_C_6") (pintype "bidirectional"))
      (node (ref "LED24") (pin "4") (pinfunction "BLUE_C_4") (pintype "bidirectional"))
      (node (ref "LED24") (pin "5") (pinfunction "RED_C_5") (pintype "bidirectional"))
      (node (ref "LED24") (pin "6") (pinfunction "GREEN_C_6") (pintype "bidirectional"))
      (node (ref "Q3") (pin "1") (pinfunction "E_1") (pintype "passive"))
    )
    (net (code "93") (name "Net-(LED17-GREEN_A)") (class "Default")
      (node (ref "LED17") (pin "1") (pinfunction "GREEN_A_1") (pintype "bidirectional"))
      (node (ref "R50") (pin "2") (pinfunction "2_2") (pintype "passive"))
    )
    (net (code "94") (name "Net-(LED17-RED_A)") (class "Default")
      (node (ref "LED17") (pin "2") (pinfunction "RED_A_2") (pintype "bidirectional"))
      (node (ref "R51") (pin "2") (pinfunction "2_2") (pintype "passive"))
    )
    (net (code "95") (name "Net-(LED18-BLUE_A)") (class "Default")
      (node (ref "LED18") (pin "3") (pinfunction "BLUE_A_3") (pintype "bidirectional"))
      (node (ref "R52") (pin "2") (pinfunction "2_2") (pintype "passive"))
    )
    (net (code "96") (name "Net-(LED18-GREEN_A)") (class "Default")
      (node (ref "LED18") (pin "1") (pinfunction "GREEN_A_1") (pintype "bidirectional"))
      (node (ref "R53") (pin "2") (pinfunction "2_2") (pintype "passive"))
    )
    (net (code "97") (name "Net-(LED18-RED_A)") (class "Default")
      (node (ref "LED18") (pin "2") (pinfunction "RED_A_2") (pintype "bidirectional"))
      (node (ref "R54") (pin "2") (pinfunction "2_2") (pintype "passive"))
    )
    (net (code "98") (name "Net-(LED19-BLUE_A)") (class "Default")
      (node (ref "LED19") (pin "3") (pinfunction "BLUE_A_3") (pintype "bidirectional"))
      (node (ref "R55") (pin "2") (pinfunction "2_2") (pintype "passive"))
    )
    (net (code "99") (name "Net-(LED19-GREEN_A)") (class "Default")
      (node (ref "LED19") (pin "1") (pinfunction "GREEN_A_1") (pintype "bidirectional"))
      (node (ref "R56") (pin "2") (pinfunction "2_2") (pintype "passive"))
    )
    (net (code "100") (name "Net-(LED19-RED_A)") (class "Default")
      (node (ref "LED19") (pin "2") (pinfunction "RED_A_2") (pintype "bidirectional"))
      (node (ref "R57") (pin "2") (pinfunction "2_2") (pintype "passive"))
    )
    (net (code "101") (name "Net-(LED20-BLUE_A)") (class "Default")
      (node (ref "LED20") (pin "3") (pinfunction "BLUE_A_3") (pintype "bidirectional"))
      (node (ref "R58") (pin "2") (pinfunction "2_2") (pintype "passive"))
    )
    (net (code "102") (name "Net-(LED20-GREEN_A)") (class "Default")
      (node (ref "LED20") (pin "1") (pinfunction "GREEN_A_1") (pintype "bidirectional"))
      (node (ref "R59") (pin "2") (pinfunction "2_2") (pintype "passive"))
    )
    (net (code "103") (name "Net-(LED20-RED_A)") (class "Default")
      (node (ref "LED20") (pin "2") (pinfunction "RED_A_2") (pintype "bidirectional"))
      (node (ref "R60") (pin "2") (pinfunction "2_2") (pintype "passive"))
    )
    (net (code "104") (name "Net-(LED21-BLUE_A)") (class "Default")
      (node (ref "LED21") (pin "3") (pinfunction "BLUE_A_3") (pintype "bidirectional"))
      (node (ref "R61") (pin "2") (pinfunction "2_2") (pintype "passive"))
    )
    (net (code "105") (name "Net-(LED21-GREEN_A)") (class "Default")
      (node (ref "LED21") (pin "1") (pinfunction "GREEN_A_1") (pintype "bidirectional"))
      (node (ref "R62") (pin "2") (pinfunction "2_2") (pintype "passive"))
    )
    (net (code "106") (name "Net-(LED21-RED_A)") (class "Default")
      (node (ref "LED21") (pin "2") (pinfunction "RED_A_2") (pintype "bidirectional"))
      (node (ref "R63") (pin "2") (pinfunction "2_2") (pintype "passive"))
    )
    (net (code "107") (name "Net-(LED22-BLUE_A)") (class "Default")
      (node (ref "LED22") (pin "3") (pinfunction "BLUE_A_3") (pintype "bidirectional"))
      (node (ref "R64") (pin "2") (pinfunction "2_2") (pintype "passive"))
    )
    (net (code "108") (name "Net-(LED22-GREEN_A)") (class "Default")
      (node (ref "LED22") (pin "1") (pinfunction "GREEN_A_1") (pintype "bidirectional"))
      (node (ref "R65") (pin "2") (pinfunction "2_2") (pintype "passive"))
    )
    (net (code "109") (name "Net-(LED22-RED_A)") (class "Default")
      (node (ref "LED22") (pin "2") (pinfunction "RED_A_2") (pintype "bidirectional"))
      (node (ref "R66") (pin "2") (pinfunction "2_2") (pintype "passive"))
    )
    (net (code "110") (name "Net-(LED23-BLUE_A)") (class "Default")
      (node (ref "LED23") (pin "3") (pinfunction "BLUE_A_3") (pintype "bidirectional"))
      (node (ref "R67") (pin "2") (pinfunction "2_2") (pintype "passive"))
    )
    (net (code "111") (name "Net-(LED23-GREEN_A)") (class "Default")
      (node (ref "LED23") (pin "1") (pinfunction "GREEN_A_1") (pintype "bidirectional"))
      (node (ref "R68") (pin "2") (pinfunction "2_2") (pintype "passive"))
    )
    (net (code "112") (name "Net-(LED23-RED_A)") (class "Default")
      (node (ref "LED23") (pin "2") (pinfunction "RED_A_2") (pintype "bidirectional"))
      (node (ref "R69") (pin "2") (pinfunction "2_2") (pintype "passive"))
    )
    (net (code "113") (name "Net-(LED24-BLUE_A)") (class "Default")
      (node (ref "LED24") (pin "3") (pinfunction "BLUE_A_3") (pintype "bidirectional"))
      (node (ref "R70") (pin "2") (pinfunction "2_2") (pintype "passive"))
    )
    (net (code "114") (name "Net-(LED24-GREEN_A)") (class "Default")
      (node (ref "LED24") (pin "1") (pinfunction "GREEN_A_1") (pintype "bidirectional"))
      (node (ref "R71") (pin "2") (pinfunction "2_2") (pintype "passive"))
    )
    (net (code "115") (name "Net-(LED24-RED_A)") (class "Default")
      (node (ref "LED24") (pin "2") (pinfunction "RED_A_2") (pintype "bidirectional"))
      (node (ref "R72") (pin "2") (pinfunction "2_2") (pintype "passive"))
    )
    (net (code "116") (name "Net-(LED25-BLUE_A)") (class "Default")
      (node (ref "LED25") (pin "3") (pinfunction "BLUE_A_3") (pintype "bidirectional"))
      (node (ref "R73") (pin "2") (pinfunction "2_2") (pintype "passive"))
    )
    (net (code "117") (name "Net-(LED25-BLUE_C)") (class "Default")
      (node (ref "LED25") (pin "4") (pinfunction "BLUE_C_4") (pintype "bidirectional"))
      (node (ref "LED25") (pin "5") (pinfunction "RED_C_5") (pintype "bidirectional"))
      (node (ref "LED25") (pin "6") (pinfunction "GREEN_C_6") (pintype "bidirectional"))
      (node (ref "LED26") (pin "4") (pinfunction "BLUE_C_4") (pintype "bidirectional"))
      (node (ref "LED26") (pin "5") (pinfunction "RED_C_5") (pintype "bidirectional"))
      (node (ref "LED26") (pin "6") (pinfunction "GREEN_C_6") (pintype "bidirectional"))
      (node (ref "LED27") (pin "4") (pinfunction "BLUE_C_4") (pintype "bidirectional"))
      (node (ref "LED27") (pin "5") (pinfunction "RED_C_5") (pintype "bidirectional"))
      (node (ref "LED27") (pin "6") (pinfunction "GREEN_C_6") (pintype "bidirectional"))
      (node (ref "LED28") (pin "4") (pinfunction "BLUE_C_4") (pintype "bidirectional"))
      (node (ref "LED28") (pin "5") (pinfunction "RED_C_5") (pintype "bidirectional"))
      (node (ref "LED28") (pin "6") (pinfunction "GREEN_C_6") (pintype "bidirectional"))
      (node (ref "LED29") (pin "4") (pinfunction "BLUE_C_4") (pintype "bidirectional"))
      (node (ref "LED29") (pin "5") (pinfunction "RED_C_5") (pintype "bidirectional"))
      (node (ref "LED29") (pin "6") (pinfunction "GREEN_C_6") (pintype "bidirectional"))
      (node (ref "LED30") (pin "4") (pinfunction "BLUE_C_4") (pintype "bidirectional"))
      (node (ref "LED30") (pin "5") (pinfunction "RED_C_5") (pintype "bidirectional"))
      (node (ref "LED30") (pin "6") (pinfunction "GREEN_C_6") (pintype "bidirectional"))
      (node (ref "LED31") (pin "4") (pinfunction "BLUE_C_4") (pintype "bidirectional"))
      (node (ref "LED31") (pin "5") (pinfunction "RED_C_5") (pintype "bidirectional"))
      (node (ref "LED31") (pin "6") (pinfunction "GREEN_C_6") (pintype "bidirectional"))
      (node (ref "LED32") (pin "4") (pinfunction "BLUE_C_4") (pintype "bidirectional"))
      (node (ref "LED32") (pin "5") (pinfunction "RED_C_5") (pintype "bidirectional"))
      (node (ref "LED32") (pin "6") (pinfunction "GREEN_C_6") (pintype "bidirectional"))
      (node (ref "Q4") (pin "1") (pinfunction "E_1") (pintype "passive"))
    )
    (net (code "118") (name "Net-(LED25-GREEN_A)") (class "Default")
      (node (ref "LED25") (pin "1") (pinfunction "GREEN_A_1") (pintype "bidirectional"))
      (node (ref "R74") (pin "2") (pinfunction "2_2") (pintype "passive"))
    )
    (net (code "119") (name "Net-(LED25-RED_A)") (class "Default")
      (node (ref "LED25") (pin "2") (pinfunction "RED_A_2") (pintype "bidirectional"))
      (node (ref "R75") (pin "2") (pinfunction "2_2") (pintype "passive"))
    )
    (net (code "120") (name "Net-(LED26-BLUE_A)") (class "Default")
      (node (ref "LED26") (pin "3") (pinfunction "BLUE_A_3") (pintype "bidirectional"))
      (node (ref "R76") (pin "2") (pinfunction "2_2") (pintype "passive"))
    )
    (net (code "121") (name "Net-(LED26-GREEN_A)") (class "Default")
      (node (ref "LED26") (pin "1") (pinfunction "GREEN_A_1") (pintype "bidirectional"))
      (node (ref "R77") (pin "2") (pinfunction "2_2") (pintype "passive"))
    )
    (net (code "122") (name "Net-(LED26-RED_A)") (class "Default")
      (node (ref "LED26") (pin "2") (pinfunction "RED_A_2") (pintype "bidirectional"))
      (node (ref "R78") (pin "2") (pinfunction "2_2") (pintype "passive"))
    )
    (net (code "123") (name "Net-(LED27-BLUE_A)") (class "Default")
      (node (ref "LED27") (pin "3") (pinfunction "BLUE_A_3") (pintype "bidirectional"))
      (node (ref "R79") (pin "2") (pinfunction "2_2") (pintype "passive"))
    )
    (net (code "124") (name "Net-(LED27-GREEN_A)") (class "Default")
      (node (ref "LED27") (pin "1") (pinfunction "GREEN_A_1") (pintype "bidirectional"))
      (node (ref "R80") (pin "2") (pinfunction "2_2") (pintype "passive"))
    )
    (net (code "125") (name "Net-(LED27-RED_A)") (class "Default")
      (node (ref "LED27") (pin "2") (pinfunction "RED_A_2") (pintype "bidirectional"))
      (node (ref "R81") (pin "2") (pinfunction "2_2") (pintype "passive"))
    )
    (net (code "126") (name "Net-(LED28-BLUE_A)") (class "Default")
      (node (ref "LED28") (pin "3") (pinfunction "BLUE_A_3") (pintype "bidirectional"))
      (node (ref "R82") (pin "2") (pinfunction "2_2") (pintype "passive"))
    )
    (net (code "127") (name "Net-(LED28-GREEN_A)") (class "Default")
      (node (ref "LED28") (pin "1") (pinfunction "GREEN_A_1") (pintype "bidirectional"))
      (node (ref "R83") (pin "2") (pinfunction "2_2") (pintype "passive"))
    )
    (net (code "128") (name "Net-(LED28-RED_A)") (class "Default")
      (node (ref "LED28") (pin "2") (pinfunction "RED_A_2") (pintype "bidirectional"))
      (node (ref "R84") (pin "2") (pinfunction "2_2") (pintype "passive"))
    )
    (net (code "129") (name "Net-(LED29-BLUE_A)") (class "Default")
      (node (ref "LED29") (pin "3") (pinfunction "BLUE_A_3") (pintype "bidirectional"))
      (node (ref "R85") (pin "2") (pinfunction "2_2") (pintype "passive"))
    )
    (net (code "130") (name "Net-(LED29-GREEN_A)") (class "Default")
      (node (ref "LED29") (pin "1") (pinfunction "GREEN_A_1") (pintype "bidirectional"))
      (node (ref "R86") (pin "2") (pinfunction "2_2") (pintype "passive"))
    )
    (net (code "131") (name "Net-(LED29-RED_A)") (class "Default")
      (node (ref "LED29") (pin "2") (pinfunction "RED_A_2") (pintype "bidirectional"))
      (node (ref "R87") (pin "2") (pinfunction "2_2") (pintype "passive"))
    )
    (net (code "132") (name "Net-(LED30-BLUE_A)") (class "Default")
      (node (ref "LED30") (pin "3") (pinfunction "BLUE_A_3") (pintype "bidirectional"))
      (node (ref "R88") (pin "2") (pinfunction "2_2") (pintype "passive"))
    )
    (net (code "133") (name "Net-(LED30-GREEN_A)") (class "Default")
      (node (ref "LED30") (pin "1") (pinfunction "GREEN_A_1") (pintype "bidirectional"))
      (node (ref "R89") (pin "2") (pinfunction "2_2") (pintype "passive"))
    )
    (net (code "134") (name "Net-(LED30-RED_A)") (class "Default")
      (node (ref "LED30") (pin "2") (pinfunction "RED_A_2") (pintype "bidirectional"))
      (node (ref "R90") (pin "2") (pinfunction "2_2") (pintype "passive"))
    )
    (net (code "135") (name "Net-(LED31-BLUE_A)") (class "Default")
      (node (ref "LED31") (pin "3") (pinfunction "BLUE_A_3") (pintype "bidirectional"))
      (node (ref "R91") (pin "2") (pinfunction "2_2") (pintype "passive"))
    )
    (net (code "136") (name "Net-(LED31-GREEN_A)") (class "Default")
      (node (ref "LED31") (pin "1") (pinfunction "GREEN_A_1") (pintype "bidirectional"))
      (node (ref "R92") (pin "2") (pinfunction "2_2") (pintype "passive"))
    )
    (net (code "137") (name "Net-(LED31-RED_A)") (class "Default")
      (node (ref "LED31") (pin "2") (pinfunction "RED_A_2") (pintype "bidirectional"))
      (node (ref "R93") (pin "2") (pinfunction "2_2") (pintype "passive"))
    )
    (net (code "138") (name "Net-(LED32-BLUE_A)") (class "Default")
      (node (ref "LED32") (pin "3") (pinfunction "BLUE_A_3") (pintype "bidirectional"))
      (node (ref "R94") (pin "2") (pinfunction "2_2") (pintype "passive"))
    )
    (net (code "139") (name "Net-(LED32-GREEN_A)") (class "Default")
      (node (ref "LED32") (pin "1") (pinfunction "GREEN_A_1") (pintype "bidirectional"))
      (node (ref "R95") (pin "2") (pinfunction "2_2") (pintype "passive"))
    )
    (net (code "140") (name "Net-(LED32-RED_A)") (class "Default")
      (node (ref "LED32") (pin "2") (pinfunction "RED_A_2") (pintype "bidirectional"))
      (node (ref "R96") (pin "2") (pinfunction "2_2") (pintype "passive"))
    )
    (net (code "141") (name "Net-(LED33-BLUE_A)") (class "Default")
      (node (ref "LED33") (pin "3") (pinfunction "BLUE_A_3") (pintype "bidirectional"))
      (node (ref "R97") (pin "2") (pinfunction "2_2") (pintype "passive"))
    )
    (net (code "142") (name "Net-(LED33-BLUE_C)") (class "Default")
      (node (ref "LED33") (pin "4") (pinfunction "BLUE_C_4") (pintype "bidirectional"))
      (node (ref "LED33") (pin "5") (pinfunction "RED_C_5") (pintype "bidirectional"))
      (node (ref "LED33") (pin "6") (pinfunction "GREEN_C_6") (pintype "bidirectional"))
      (node (ref "LED34") (pin "4") (pinfunction "BLUE_C_4") (pintype "bidirectional"))
      (node (ref "LED34") (pin "5") (pinfunction "RED_C_5") (pintype "bidirectional"))
      (node (ref "LED34") (pin "6") (pinfunction "GREEN_C_6") (pintype "bidirectional"))
      (node (ref "LED35") (pin "4") (pinfunction "BLUE_C_4") (pintype "bidirectional"))
      (node (ref "LED35") (pin "5") (pinfunction "RED_C_5") (pintype "bidirectional"))
      (node (ref "LED35") (pin "6") (pinfunction "GREEN_C_6") (pintype "bidirectional"))
      (node (ref "LED36") (pin "4") (pinfunction "BLUE_C_4") (pintype "bidirectional"))
      (node (ref "LED36") (pin "5") (pinfunction "RED_C_5") (pintype "bidirectional"))
      (node (ref "LED36") (pin "6") (pinfunction "GREEN_C_6") (pintype "bidirectional"))
      (node (ref "LED37") (pin "4") (pinfunction "BLUE_C_4") (pintype "bidirectional"))
      (node (ref "LED37") (pin "5") (pinfunction "RED_C_5") (pintype "bidirectional"))
      (node (ref "LED37") (pin "6") (pinfunction "GREEN_C_6") (pintype "bidirectional"))
      (node (ref "LED38") (pin "4") (pinfunction "BLUE_C_4") (pintype "bidirectional"))
      (node (ref "LED38") (pin "5") (pinfunction "RED_C_5") (pintype "bidirectional"))
      (node (ref "LED38") (pin "6") (pinfunction "GREEN_C_6") (pintype "bidirectional"))
      (node (ref "LED39") (pin "4") (pinfunction "BLUE_C_4") (pintype "bidirectional"))
      (node (ref "LED39") (pin "5") (pinfunction "RED_C_5") (pintype "bidirectional"))
      (node (ref "LED39") (pin "6") (pinfunction "GREEN_C_6") (pintype "bidirectional"))
      (node (ref "LED40") (pin "4") (pinfunction "BLUE_C_4") (pintype "bidirectional"))
      (node (ref "LED40") (pin "5") (pinfunction "RED_C_5") (pintype "bidirectional"))
      (node (ref "LED40") (pin "6") (pinfunction "GREEN_C_6") (pintype "bidirectional"))
      (node (ref "Q5") (pin "1") (pinfunction "E_1") (pintype "passive"))
    )
    (net (code "143") (name "Net-(LED33-GREEN_A)") (class "Default")
      (node (ref "LED33") (pin "1") (pinfunction "GREEN_A_1") (pintype "bidirectional"))
      (node (ref "R98") (pin "2") (pinfunction "2_2") (pintype "passive"))
    )
    (net (code "144") (name "Net-(LED33-RED_A)") (class "Default")
      (node (ref "LED33") (pin "2") (pinfunction "RED_A_2") (pintype "bidirectional"))
      (node (ref "R99") (pin "2") (pinfunction "2_2") (pintype "passive"))
    )
    (net (code "145") (name "Net-(LED34-BLUE_A)") (class "Default")
      (node (ref "LED34") (pin "3") (pinfunction "BLUE_A_3") (pintype "bidirectional"))
      (node (ref "R100") (pin "2") (pinfunction "2_2") (pintype "passive"))
    )
    (net (code "146") (name "Net-(LED34-GREEN_A)") (class "Default")
      (node (ref "LED34") (pin "1") (pinfunction "GREEN_A_1") (pintype "bidirectional"))
      (node (ref "R101") (pin "2") (pinfunction "2_2") (pintype "passive"))
    )
    (net (code "147") (name "Net-(LED34-RED_A)") (class "Default")
      (node (ref "LED34") (pin "2") (pinfunction "RED_A_2") (pintype "bidirectional"))
      (node (ref "R102") (pin "2") (pinfunction "2_2") (pintype "passive"))
    )
    (net (code "148") (name "Net-(LED35-BLUE_A)") (class "Default")
      (node (ref "LED35") (pin "3") (pinfunction "BLUE_A_3") (pintype "bidirectional"))
      (node (ref "R103") (pin "2") (pinfunction "2_2") (pintype "passive"))
    )
    (net (code "149") (name "Net-(LED35-GREEN_A)") (class "Default")
      (node (ref "LED35") (pin "1") (pinfunction "GREEN_A_1") (pintype "bidirectional"))
      (node (ref "R104") (pin "2") (pinfunction "2_2") (pintype "passive"))
    )
    (net (code "150") (name "Net-(LED35-RED_A)") (class "Default")
      (node (ref "LED35") (pin "2") (pinfunction "RED_A_2") (pintype "bidirectional"))
      (node (ref "R105") (pin "2") (pinfunction "2_2") (pintype "passive"))
    )
    (net (code "151") (name "Net-(LED36-BLUE_A)") (class "Default")
      (node (ref "LED36") (pin "3") (pinfunction "BLUE_A_3") (pintype "bidirectional"))
      (node (ref "R106") (pin "2") (pinfunction "2_2") (pintype "passive"))
    )
    (net (code "152") (name "Net-(LED36-GREEN_A)") (class "Default")
      (node (ref "LED36") (pin "1") (pinfunction "GREEN_A_1") (pintype "bidirectional"))
      (node (ref "R107") (pin "2") (pinfunction "2_2") (pintype "passive"))
    )
    (net (code "153") (name "Net-(LED36-RED_A)") (class "Default")
      (node (ref "LED36") (pin "2") (pinfunction "RED_A_2") (pintype "bidirectional"))
      (node (ref "R108") (pin "2") (pinfunction "2_2") (pintype "passive"))
    )
    (net (code "154") (name "Net-(LED37-BLUE_A)") (class "Default")
      (node (ref "LED37") (pin "3") (pinfunction "BLUE_A_3") (pintype "bidirectional"))
      (node (ref "R109") (pin "2") (pinfunction "2_2") (pintype "passive"))
    )
    (net (code "155") (name "Net-(LED37-GREEN_A)") (class "Default")
      (node (ref "LED37") (pin "1") (pinfunction "GREEN_A_1") (pintype "bidirectional"))
      (node (ref "R110") (pin "2") (pinfunction "2_2") (pintype "passive"))
    )
    (net (code "156") (name "Net-(LED37-RED_A)") (class "Default")
      (node (ref "LED37") (pin "2") (pinfunction "RED_A_2") (pintype "bidirectional"))
      (node (ref "R111") (pin "2") (pinfunction "2_2") (pintype "passive"))
    )
    (net (code "157") (name "Net-(LED38-BLUE_A)") (class "Default")
      (node (ref "LED38") (pin "3") (pinfunction "BLUE_A_3") (pintype "bidirectional"))
      (node (ref "R112") (pin "2") (pinfunction "2_2") (pintype "passive"))
    )
    (net (code "158") (name "Net-(LED38-GREEN_A)") (class "Default")
      (node (ref "LED38") (pin "1") (pinfunction "GREEN_A_1") (pintype "bidirectional"))
      (node (ref "R113") (pin "2") (pinfunction "2_2") (pintype "passive"))
    )
    (net (code "159") (name "Net-(LED38-RED_A)") (class "Default")
      (node (ref "LED38") (pin "2") (pinfunction "RED_A_2") (pintype "bidirectional"))
      (node (ref "R114") (pin "2") (pinfunction "2_2") (pintype "passive"))
    )
    (net (code "160") (name "Net-(LED39-BLUE_A)") (class "Default")
      (node (ref "LED39") (pin "3") (pinfunction "BLUE_A_3") (pintype "bidirectional"))
      (node (ref "R115") (pin "2") (pinfunction "2_2") (pintype "passive"))
    )
    (net (code "161") (name "Net-(LED39-GREEN_A)") (class "Default")
      (node (ref "LED39") (pin "1") (pinfunction "GREEN_A_1") (pintype "bidirectional"))
      (node (ref "R116") (pin "2") (pinfunction "2_2") (pintype "passive"))
    )
    (net (code "162") (name "Net-(LED39-RED_A)") (class "Default")
      (node (ref "LED39") (pin "2") (pinfunction "RED_A_2") (pintype "bidirectional"))
      (node (ref "R117") (pin "2") (pinfunction "2_2") (pintype "passive"))
    )
    (net (code "163") (name "Net-(LED40-BLUE_A)") (class "Default")
      (node (ref "LED40") (pin "3") (pinfunction "BLUE_A_3") (pintype "bidirectional"))
      (node (ref "R118") (pin "2") (pinfunction "2_2") (pintype "passive"))
    )
    (net (code "164") (name "Net-(LED40-GREEN_A)") (class "Default")
      (node (ref "LED40") (pin "1") (pinfunction "GREEN_A_1") (pintype "bidirectional"))
      (node (ref "R119") (pin "2") (pinfunction "2_2") (pintype "passive"))
    )
    (net (code "165") (name "Net-(LED40-RED_A)") (class "Default")
      (node (ref "LED40") (pin "2") (pinfunction "RED_A_2") (pintype "bidirectional"))
      (node (ref "R120") (pin "2") (pinfunction "2_2") (pintype "passive"))
    )
    (net (code "166") (name "Net-(LED41-BLUE_A)") (class "Default")
      (node (ref "LED41") (pin "3") (pinfunction "BLUE_A_3") (pintype "bidirectional"))
      (node (ref "R121") (pin "2") (pinfunction "2_2") (pintype "passive"))
    )
    (net (code "167") (name "Net-(LED41-BLUE_C)") (class "Default")
      (node (ref "LED41") (pin "4") (pinfunction "BLUE_C_4") (pintype "bidirectional"))
      (node (ref "LED41") (pin "5") (pinfunction "RED_C_5") (pintype "bidirectional"))
      (node (ref "LED41") (pin "6") (pinfunction "GREEN_C_6") (pintype "bidirectional"))
      (node (ref "LED42") (pin "4") (pinfunction "BLUE_C_4") (pintype "bidirectional"))
      (node (ref "LED42") (pin "5") (pinfunction "RED_C_5") (pintype "bidirectional"))
      (node (ref "LED42") (pin "6") (pinfunction "GREEN_C_6") (pintype "bidirectional"))
      (node (ref "LED43") (pin "4") (pinfunction "BLUE_C_4") (pintype "bidirectional"))
      (node (ref "LED43") (pin "5") (pinfunction "RED_C_5") (pintype "bidirectional"))
      (node (ref "LED43") (pin "6") (pinfunction "GREEN_C_6") (pintype "bidirectional"))
      (node (ref "LED44") (pin "4") (pinfunction "BLUE_C_4") (pintype "bidirectional"))
      (node (ref "LED44") (pin "5") (pinfunction "RED_C_5") (pintype "bidirectional"))
      (node (ref "LED44") (pin "6") (pinfunction "GREEN_C_6") (pintype "bidirectional"))
      (node (ref "LED45") (pin "4") (pinfunction "BLUE_C_4") (pintype "bidirectional"))
      (node (ref "LED45") (pin "5") (pinfunction "RED_C_5") (pintype "bidirectional"))
      (node (ref "LED45") (pin "6") (pinfunction "GREEN_C_6") (pintype "bidirectional"))
      (node (ref "LED46") (pin "4") (pinfunction "BLUE_C_4") (pintype "bidirectional"))
      (node (ref "LED46") (pin "5") (pinfunction "RED_C_5") (pintype "bidirectional"))
      (node (ref "LED46") (pin "6") (pinfunction "GREEN_C_6") (pintype "bidirectional"))
      (node (ref "LED47") (pin "4") (pinfunction "BLUE_C_4") (pintype "bidirectional"))
      (node (ref "LED47") (pin "5") (pinfunction "RED_C_5") (pintype "bidirectional"))
      (node (ref "LED47") (pin "6") (pinfunction "GREEN_C_6") (pintype "bidirectional"))
      (node (ref "LED48") (pin "4") (pinfunction "BLUE_C_4") (pintype "bidirectional"))
      (node (ref "LED48") (pin "5") (pinfunction "RED_C_5") (pintype "bidirectional"))
      (node (ref "LED48") (pin "6") (pinfunction "GREEN_C_6") (pintype "bidirectional"))
      (node (ref "Q6") (pin "1") (pinfunction "E_1") (pintype "passive"))
    )
    (net (code "168") (name "Net-(LED41-GREEN_A)") (class "Default")
      (node (ref "LED41") (pin "1") (pinfunction "GREEN_A_1") (pintype "bidirectional"))
      (node (ref "R122") (pin "2") (pinfunction "2_2") (pintype "passive"))
    )
    (net (code "169") (name "Net-(LED41-RED_A)") (class "Default")
      (node (ref "LED41") (pin "2") (pinfunction "RED_A_2") (pintype "bidirectional"))
      (node (ref "R123") (pin "2") (pinfunction "2_2") (pintype "passive"))
    )
    (net (code "170") (name "Net-(LED42-BLUE_A)") (class "Default")
      (node (ref "LED42") (pin "3") (pinfunction "BLUE_A_3") (pintype "bidirectional"))
      (node (ref "R124") (pin "2") (pinfunction "2_2") (pintype "passive"))
    )
    (net (code "171") (name "Net-(LED42-GREEN_A)") (class "Default")
      (node (ref "LED42") (pin "1") (pinfunction "GREEN_A_1") (pintype "bidirectional"))
      (node (ref "R125") (pin "2") (pinfunction "2_2") (pintype "passive"))
    )
    (net (code "172") (name "Net-(LED42-RED_A)") (class "Default")
      (node (ref "LED42") (pin "2") (pinfunction "RED_A_2") (pintype "bidirectional"))
      (node (ref "R126") (pin "2") (pinfunction "2_2") (pintype "passive"))
    )
    (net (code "173") (name "Net-(LED43-BLUE_A)") (class "Default")
      (node (ref "LED43") (pin "3") (pinfunction "BLUE_A_3") (pintype "bidirectional"))
      (node (ref "R127") (pin "2") (pinfunction "2_2") (pintype "passive"))
    )
    (net (code "174") (name "Net-(LED43-GREEN_A)") (class "Default")
      (node (ref "LED43") (pin "1") (pinfunction "GREEN_A_1") (pintype "bidirectional"))
      (node (ref "R128") (pin "2") (pinfunction "2_2") (pintype "passive"))
    )
    (net (code "175") (name "Net-(LED43-RED_A)") (class "Default")
      (node (ref "LED43") (pin "2") (pinfunction "RED_A_2") (pintype "bidirectional"))
      (node (ref "R129") (pin "2") (pinfunction "2_2") (pintype "passive"))
    )
    (net (code "176") (name "Net-(LED44-BLUE_A)") (class "Default")
      (node (ref "LED44") (pin "3") (pinfunction "BLUE_A_3") (pintype "bidirectional"))
      (node (ref "R130") (pin "2") (pinfunction "2_2") (pintype "passive"))
    )
    (net (code "177") (name "Net-(LED44-GREEN_A)") (class "Default")
      (node (ref "LED44") (pin "1") (pinfunction "GREEN_A_1") (pintype "bidirectional"))
      (node (ref "R131") (pin "2") (pinfunction "2_2") (pintype "passive"))
    )
    (net (code "178") (name "Net-(LED44-RED_A)") (class "Default")
      (node (ref "LED44") (pin "2") (pinfunction "RED_A_2") (pintype "bidirectional"))
      (node (ref "R132") (pin "2") (pinfunction "2_2") (pintype "passive"))
    )
    (net (code "179") (name "Net-(LED45-BLUE_A)") (class "Default")
      (node (ref "LED45") (pin "3") (pinfunction "BLUE_A_3") (pintype "bidirectional"))
      (node (ref "R133") (pin "2") (pinfunction "2_2") (pintype "passive"))
    )
    (net (code "180") (name "Net-(LED45-GREEN_A)") (class "Default")
      (node (ref "LED45") (pin "1") (pinfunction "GREEN_A_1") (pintype "bidirectional"))
      (node (ref "R134") (pin "2") (pinfunction "2_2") (pintype "passive"))
    )
    (net (code "181") (name "Net-(LED45-RED_A)") (class "Default")
      (node (ref "LED45") (pin "2") (pinfunction "RED_A_2") (pintype "bidirectional"))
      (node (ref "R135") (pin "2") (pinfunction "2_2") (pintype "passive"))
    )
    (net (code "182") (name "Net-(LED46-BLUE_A)") (class "Default")
      (node (ref "LED46") (pin "3") (pinfunction "BLUE_A_3") (pintype "bidirectional"))
      (node (ref "R136") (pin "2") (pinfunction "2_2") (pintype "passive"))
    )
    (net (code "183") (name "Net-(LED46-GREEN_A)") (class "Default")
      (node (ref "LED46") (pin "1") (pinfunction "GREEN_A_1") (pintype "bidirectional"))
      (node (ref "R137") (pin "2") (pinfunction "2_2") (pintype "passive"))
    )
    (net (code "184") (name "Net-(LED46-RED_A)") (class "Default")
      (node (ref "LED46") (pin "2") (pinfunction "RED_A_2") (pintype "bidirectional"))
      (node (ref "R138") (pin "2") (pinfunction "2_2") (pintype "passive"))
    )
    (net (code "185") (name "Net-(LED47-BLUE_A)") (class "Default")
      (node (ref "LED47") (pin "3") (pinfunction "BLUE_A_3") (pintype "bidirectional"))
      (node (ref "R139") (pin "2") (pinfunction "2_2") (pintype "passive"))
    )
    (net (code "186") (name "Net-(LED47-GREEN_A)") (class "Default")
      (node (ref "LED47") (pin "1") (pinfunction "GREEN_A_1") (pintype "bidirectional"))
      (node (ref "R140") (pin "2") (pinfunction "2_2") (pintype "passive"))
    )
    (net (code "187") (name "Net-(LED47-RED_A)") (class "Default")
      (node (ref "LED47") (pin "2") (pinfunction "RED_A_2") (pintype "bidirectional"))
      (node (ref "R141") (pin "2") (pinfunction "2_2") (pintype "passive"))
    )
    (net (code "188") (name "Net-(LED48-BLUE_A)") (class "Default")
      (node (ref "LED48") (pin "3") (pinfunction "BLUE_A_3") (pintype "bidirectional"))
      (node (ref "R142") (pin "2") (pinfunction "2_2") (pintype "passive"))
    )
    (net (code "189") (name "Net-(LED48-GREEN_A)") (class "Default")
      (node (ref "LED48") (pin "1") (pinfunction "GREEN_A_1") (pintype "bidirectional"))
      (node (ref "R143") (pin "2") (pinfunction "2_2") (pintype "passive"))
    )
    (net (code "190") (name "Net-(LED48-RED_A)") (class "Default")
      (node (ref "LED48") (pin "2") (pinfunction "RED_A_2") (pintype "bidirectional"))
      (node (ref "R144") (pin "2") (pinfunction "2_2") (pintype "passive"))
    )
    (net (code "191") (name "Net-(LED49-BLUE_A)") (class "Default")
      (node (ref "LED49") (pin "3") (pinfunction "BLUE_A_3") (pintype "bidirectional"))
      (node (ref "R145") (pin "2") (pinfunction "2_2") (pintype "passive"))
    )
    (net (code "192") (name "Net-(LED49-BLUE_C)") (class "Default")
      (node (ref "LED49") (pin "4") (pinfunction "BLUE_C_4") (pintype "bidirectional"))
      (node (ref "LED49") (pin "5") (pinfunction "RED_C_5") (pintype "bidirectional"))
      (node (ref "LED49") (pin "6") (pinfunction "GREEN_C_6") (pintype "bidirectional"))
      (node (ref "LED50") (pin "4") (pinfunction "BLUE_C_4") (pintype "bidirectional"))
      (node (ref "LED50") (pin "5") (pinfunction "RED_C_5") (pintype "bidirectional"))
      (node (ref "LED50") (pin "6") (pinfunction "GREEN_C_6") (pintype "bidirectional"))
      (node (ref "LED51") (pin "4") (pinfunction "BLUE_C_4") (pintype "bidirectional"))
      (node (ref "LED51") (pin "5") (pinfunction "RED_C_5") (pintype "bidirectional"))
      (node (ref "LED51") (pin "6") (pinfunction "GREEN_C_6") (pintype "bidirectional"))
      (node (ref "LED52") (pin "4") (pinfunction "BLUE_C_4") (pintype "bidirectional"))
      (node (ref "LED52") (pin "5") (pinfunction "RED_C_5") (pintype "bidirectional"))
      (node (ref "LED52") (pin "6") (pinfunction "GREEN_C_6") (pintype "bidirectional"))
      (node (ref "LED53") (pin "4") (pinfunction "BLUE_C_4") (pintype "bidirectional"))
      (node (ref "LED53") (pin "5") (pinfunction "RED_C_5") (pintype "bidirectional"))
      (node (ref "LED53") (pin "6") (pinfunction "GREEN_C_6") (pintype "bidirectional"))
      (node (ref "LED54") (pin "4") (pinfunction "BLUE_C_4") (pintype "bidirectional"))
      (node (ref "LED54") (pin "5") (pinfunction "RED_C_5") (pintype "bidirectional"))
      (node (ref "LED54") (pin "6") (pinfunction "GREEN_C_6") (pintype "bidirectional"))
      (node (ref "LED55") (pin "4") (pinfunction "BLUE_C_4") (pintype "bidirectional"))
      (node (ref "LED55") (pin "5") (pinfunction "RED_C_5") (pintype "bidirectional"))
      (node (ref "LED55") (pin "6") (pinfunction "GREEN_C_6") (pintype "bidirectional"))
      (node (ref "LED56") (pin "4") (pinfunction "BLUE_C_4") (pintype "bidirectional"))
      (node (ref "LED56") (pin "5") (pinfunction "RED_C_5") (pintype "bidirectional"))
      (node (ref "LED56") (pin "6") (pinfunction "GREEN_C_6") (pintype "bidirectional"))
      (node (ref "Q7") (pin "1") (pinfunction "E_1") (pintype "passive"))
    )
    (net (code "193") (name "Net-(LED49-GREEN_A)") (class "Default")
      (node (ref "LED49") (pin "1") (pinfunction "GREEN_A_1") (pintype "bidirectional"))
      (node (ref "R146") (pin "2") (pinfunction "2_2") (pintype "passive"))
    )
    (net (code "194") (name "Net-(LED49-RED_A)") (class "Default")
      (node (ref "LED49") (pin "2") (pinfunction "RED_A_2") (pintype "bidirectional"))
      (node (ref "R147") (pin "2") (pinfunction "2_2") (pintype "passive"))
    )
    (net (code "195") (name "Net-(LED50-BLUE_A)") (class "Default")
      (node (ref "LED50") (pin "3") (pinfunction "BLUE_A_3") (pintype "bidirectional"))
      (node (ref "R148") (pin "2") (pinfunction "2_2") (pintype "passive"))
    )
    (net (code "196") (name "Net-(LED50-GREEN_A)") (class "Default")
      (node (ref "LED50") (pin "1") (pinfunction "GREEN_A_1") (pintype "bidirectional"))
      (node (ref "R149") (pin "2") (pinfunction "2_2") (pintype "passive"))
    )
    (net (code "197") (name "Net-(LED50-RED_A)") (class "Default")
      (node (ref "LED50") (pin "2") (pinfunction "RED_A_2") (pintype "bidirectional"))
      (node (ref "R150") (pin "2") (pinfunction "2_2") (pintype "passive"))
    )
    (net (code "198") (name "Net-(LED51-BLUE_A)") (class "Default")
      (node (ref "LED51") (pin "3") (pinfunction "BLUE_A_3") (pintype "bidirectional"))
      (node (ref "R151") (pin "2") (pinfunction "2_2") (pintype "passive"))
    )
    (net (code "199") (name "Net-(LED51-GREEN_A)") (class "Default")
      (node (ref "LED51") (pin "1") (pinfunction "GREEN_A_1") (pintype "bidirectional"))
      (node (ref "R152") (pin "2") (pinfunction "2_2") (pintype "passive"))
    )
    (net (code "200") (name "Net-(LED51-RED_A)") (class "Default")
      (node (ref "LED51") (pin "2") (pinfunction "RED_A_2") (pintype "bidirectional"))
      (node (ref "R153") (pin "2") (pinfunction "2_2") (pintype "passive"))
    )
    (net (code "201") (name "Net-(LED52-BLUE_A)") (class "Default")
      (node (ref "LED52") (pin "3") (pinfunction "BLUE_A_3") (pintype "bidirectional"))
      (node (ref "R154") (pin "2") (pinfunction "2_2") (pintype "passive"))
    )
    (net (code "202") (name "Net-(LED52-GREEN_A)") (class "Default")
      (node (ref "LED52") (pin "1") (pinfunction "GREEN_A_1") (pintype "bidirectional"))
      (node (ref "R155") (pin "2") (pinfunction "2_2") (pintype "passive"))
    )
    (net (code "203") (name "Net-(LED52-RED_A)") (class "Default")
      (node (ref "LED52") (pin "2") (pinfunction "RED_A_2") (pintype "bidirectional"))
      (node (ref "R156") (pin "2") (pinfunction "2_2") (pintype "passive"))
    )
    (net (code "204") (name "Net-(LED53-BLUE_A)") (class "Default")
      (node (ref "LED53") (pin "3") (pinfunction "BLUE_A_3") (pintype "bidirectional"))
      (node (ref "R157") (pin "2") (pinfunction "2_2") (pintype "passive"))
    )
    (net (code "205") (name "Net-(LED53-GREEN_A)") (class "Default")
      (node (ref "LED53") (pin "1") (pinfunction "GREEN_A_1") (pintype "bidirectional"))
      (node (ref "R158") (pin "2") (pinfunction "2_2") (pintype "passive"))
    )
    (net (code "206") (name "Net-(LED53-RED_A)") (class "Default")
      (node (ref "LED53") (pin "2") (pinfunction "RED_A_2") (pintype "bidirectional"))
      (node (ref "R159") (pin "2") (pinfunction "2_2") (pintype "passive"))
    )
    (net (code "207") (name "Net-(LED54-BLUE_A)") (class "Default")
      (node (ref "LED54") (pin "3") (pinfunction "BLUE_A_3") (pintype "bidirectional"))
      (node (ref "R160") (pin "2") (pinfunction "2_2") (pintype "passive"))
    )
    (net (code "208") (name "Net-(LED54-GREEN_A)") (class "Default")
      (node (ref "LED54") (pin "1") (pinfunction "GREEN_A_1") (pintype "bidirectional"))
      (node (ref "R161") (pin "2") (pinfunction "2_2") (pintype "passive"))
    )
    (net (code "209") (name "Net-(LED54-RED_A)") (class "Default")
      (node (ref "LED54") (pin "2") (pinfunction "RED_A_2") (pintype "bidirectional"))
      (node (ref "R162") (pin "2") (pinfunction "2_2") (pintype "passive"))
    )
    (net (code "210") (name "Net-(LED55-BLUE_A)") (class "Default")
      (node (ref "LED55") (pin "3") (pinfunction "BLUE_A_3") (pintype "bidirectional"))
      (node (ref "R163") (pin "2") (pinfunction "2_2") (pintype "passive"))
    )
    (net (code "211") (name "Net-(LED55-GREEN_A)") (class "Default")
      (node (ref "LED55") (pin "1") (pinfunction "GREEN_A_1") (pintype "bidirectional"))
      (node (ref "R164") (pin "2") (pinfunction "2_2") (pintype "passive"))
    )
    (net (code "212") (name "Net-(LED55-RED_A)") (class "Default")
      (node (ref "LED55") (pin "2") (pinfunction "RED_A_2") (pintype "bidirectional"))
      (node (ref "R165") (pin "2") (pinfunction "2_2") (pintype "passive"))
    )
    (net (code "213") (name "Net-(LED56-BLUE_A)") (class "Default")
      (node (ref "LED56") (pin "3") (pinfunction "BLUE_A_3") (pintype "bidirectional"))
      (node (ref "R166") (pin "2") (pinfunction "2_2") (pintype "passive"))
    )
    (net (code "214") (name "Net-(LED56-GREEN_A)") (class "Default")
      (node (ref "LED56") (pin "1") (pinfunction "GREEN_A_1") (pintype "bidirectional"))
      (node (ref "R167") (pin "2") (pinfunction "2_2") (pintype "passive"))
    )
    (net (code "215") (name "Net-(LED56-RED_A)") (class "Default")
      (node (ref "LED56") (pin "2") (pinfunction "RED_A_2") (pintype "bidirectional"))
      (node (ref "R168") (pin "2") (pinfunction "2_2") (pintype "passive"))
    )
    (net (code "216") (name "Net-(LED57-BLUE_A)") (class "Default")
      (node (ref "LED57") (pin "3") (pinfunction "BLUE_A_3") (pintype "bidirectional"))
      (node (ref "R169") (pin "2") (pinfunction "2_2") (pintype "passive"))
    )
    (net (code "217") (name "Net-(LED57-BLUE_C)") (class "Default")
      (node (ref "LED57") (pin "4") (pinfunction "BLUE_C_4") (pintype "bidirectional"))
      (node (ref "LED57") (pin "5") (pinfunction "RED_C_5") (pintype "bidirectional"))
      (node (ref "LED57") (pin "6") (pinfunction "GREEN_C_6") (pintype "bidirectional"))
      (node (ref "LED58") (pin "4") (pinfunction "BLUE_C_4") (pintype "bidirectional"))
      (node (ref "LED58") (pin "5") (pinfunction "RED_C_5") (pintype "bidirectional"))
      (node (ref "LED58") (pin "6") (pinfunction "GREEN_C_6") (pintype "bidirectional"))
      (node (ref "LED59") (pin "4") (pinfunction "BLUE_C_4") (pintype "bidirectional"))
      (node (ref "LED59") (pin "5") (pinfunction "RED_C_5") (pintype "bidirectional"))
      (node (ref "LED59") (pin "6") (pinfunction "GREEN_C_6") (pintype "bidirectional"))
      (node (ref "LED60") (pin "4") (pinfunction "BLUE_C_4") (pintype "bidirectional"))
      (node (ref "LED60") (pin "5") (pinfunction "RED_C_5") (pintype "bidirectional"))
      (node (ref "LED60") (pin "6") (pinfunction "GREEN_C_6") (pintype "bidirectional"))
      (node (ref "LED61") (pin "4") (pinfunction "BLUE_C_4") (pintype "bidirectional"))
      (node (ref "LED61") (pin "5") (pinfunction "RED_C_5") (pintype "bidirectional"))
      (node (ref "LED61") (pin "6") (pinfunction "GREEN_C_6") (pintype "bidirectional"))
      (node (ref "LED62") (pin "4") (pinfunction "BLUE_C_4") (pintype "bidirectional"))
      (node (ref "LED62") (pin "5") (pinfunction "RED_C_5") (pintype "bidirectional"))
      (node (ref "LED62") (pin "6") (pinfunction "GREEN_C_6") (pintype "bidirectional"))
      (node (ref "LED63") (pin "4") (pinfunction "BLUE_C_4") (pintype "bidirectional"))
      (node (ref "LED63") (pin "5") (pinfunction "RED_C_5") (pintype "bidirectional"))
      (node (ref "LED63") (pin "6") (pinfunction "GREEN_C_6") (pintype "bidirectional"))
      (node (ref "LED64") (pin "4") (pinfunction "BLUE_C_4") (pintype "bidirectional"))
      (node (ref "LED64") (pin "5") (pinfunction "RED_C_5") (pintype "bidirectional"))
      (node (ref "LED64") (pin "6") (pinfunction "GREEN_C_6") (pintype "bidirectional"))
      (node (ref "Q8") (pin "1") (pinfunction "E_1") (pintype "passive"))
    )
    (net (code "218") (name "Net-(LED57-GREEN_A)") (class "Default")
      (node (ref "LED57") (pin "1") (pinfunction "GREEN_A_1") (pintype "bidirectional"))
      (node (ref "R170") (pin "2") (pinfunction "2_2") (pintype "passive"))
    )
    (net (code "219") (name "Net-(LED57-RED_A)") (class "Default")
      (node (ref "LED57") (pin "2") (pinfunction "RED_A_2") (pintype "bidirectional"))
      (node (ref "R171") (pin "2") (pinfunction "2_2") (pintype "passive"))
    )
    (net (code "220") (name "Net-(LED58-BLUE_A)") (class "Default")
      (node (ref "LED58") (pin "3") (pinfunction "BLUE_A_3") (pintype "bidirectional"))
      (node (ref "R172") (pin "2") (pinfunction "2_2") (pintype "passive"))
    )
    (net (code "221") (name "Net-(LED58-GREEN_A)") (class "Default")
      (node (ref "LED58") (pin "1") (pinfunction "GREEN_A_1") (pintype "bidirectional"))
      (node (ref "R173") (pin "2") (pinfunction "2_2") (pintype "passive"))
    )
    (net (code "222") (name "Net-(LED58-RED_A)") (class "Default")
      (node (ref "LED58") (pin "2") (pinfunction "RED_A_2") (pintype "bidirectional"))
      (node (ref "R174") (pin "2") (pinfunction "2_2") (pintype "passive"))
    )
    (net (code "223") (name "Net-(LED59-BLUE_A)") (class "Default")
      (node (ref "LED59") (pin "3") (pinfunction "BLUE_A_3") (pintype "bidirectional"))
      (node (ref "R175") (pin "2") (pinfunction "2_2") (pintype "passive"))
    )
    (net (code "224") (name "Net-(LED59-GREEN_A)") (class "Default")
      (node (ref "LED59") (pin "1") (pinfunction "GREEN_A_1") (pintype "bidirectional"))
      (node (ref "R176") (pin "2") (pinfunction "2_2") (pintype "passive"))
    )
    (net (code "225") (name "Net-(LED59-RED_A)") (class "Default")
      (node (ref "LED59") (pin "2") (pinfunction "RED_A_2") (pintype "bidirectional"))
      (node (ref "R177") (pin "2") (pinfunction "2_2") (pintype "passive"))
    )
    (net (code "226") (name "Net-(LED60-BLUE_A)") (class "Default")
      (node (ref "LED60") (pin "3") (pinfunction "BLUE_A_3") (pintype "bidirectional"))
      (node (ref "R178") (pin "2") (pinfunction "2_2") (pintype "passive"))
    )
    (net (code "227") (name "Net-(LED60-GREEN_A)") (class "Default")
      (node (ref "LED60") (pin "1") (pinfunction "GREEN_A_1") (pintype "bidirectional"))
      (node (ref "R179") (pin "2") (pinfunction "2_2") (pintype "passive"))
    )
    (net (code "228") (name "Net-(LED60-RED_A)") (class "Default")
      (node (ref "LED60") (pin "2") (pinfunction "RED_A_2") (pintype "bidirectional"))
      (node (ref "R180") (pin "2") (pinfunction "2_2") (pintype "passive"))
    )
    (net (code "229") (name "Net-(LED61-BLUE_A)") (class "Default")
      (node (ref "LED61") (pin "3") (pinfunction "BLUE_A_3") (pintype "bidirectional"))
      (node (ref "R181") (pin "2") (pinfunction "2_2") (pintype "passive"))
    )
    (net (code "230") (name "Net-(LED61-GREEN_A)") (class "Default")
      (node (ref "LED61") (pin "1") (pinfunction "GREEN_A_1") (pintype "bidirectional"))
      (node (ref "R182") (pin "2") (pinfunction "2_2") (pintype "passive"))
    )
    (net (code "231") (name "Net-(LED61-RED_A)") (class "Default")
      (node (ref "LED61") (pin "2") (pinfunction "RED_A_2") (pintype "bidirectional"))
      (node (ref "R183") (pin "2") (pinfunction "2_2") (pintype "passive"))
    )
    (net (code "232") (name "Net-(LED62-BLUE_A)") (class "Default")
      (node (ref "LED62") (pin "3") (pinfunction "BLUE_A_3") (pintype "bidirectional"))
      (node (ref "R184") (pin "2") (pinfunction "2_2") (pintype "passive"))
    )
    (net (code "233") (name "Net-(LED62-GREEN_A)") (class "Default")
      (node (ref "LED62") (pin "1") (pinfunction "GREEN_A_1") (pintype "bidirectional"))
      (node (ref "R185") (pin "2") (pinfunction "2_2") (pintype "passive"))
    )
    (net (code "234") (name "Net-(LED62-RED_A)") (class "Default")
      (node (ref "LED62") (pin "2") (pinfunction "RED_A_2") (pintype "bidirectional"))
      (node (ref "R186") (pin "2") (pinfunction "2_2") (pintype "passive"))
    )
    (net (code "235") (name "Net-(LED63-BLUE_A)") (class "Default")
      (node (ref "LED63") (pin "3") (pinfunction "BLUE_A_3") (pintype "bidirectional"))
      (node (ref "R187") (pin "2") (pinfunction "2_2") (pintype "passive"))
    )
    (net (code "236") (name "Net-(LED63-GREEN_A)") (class "Default")
      (node (ref "LED63") (pin "1") (pinfunction "GREEN_A_1") (pintype "bidirectional"))
      (node (ref "R188") (pin "2") (pinfunction "2_2") (pintype "passive"))
    )
    (net (code "237") (name "Net-(LED63-RED_A)") (class "Default")
      (node (ref "LED63") (pin "2") (pinfunction "RED_A_2") (pintype "bidirectional"))
      (node (ref "R189") (pin "2") (pinfunction "2_2") (pintype "passive"))
    )
    (net (code "238") (name "Net-(LED64-BLUE_A)") (class "Default")
      (node (ref "LED64") (pin "3") (pinfunction "BLUE_A_3") (pintype "bidirectional"))
      (node (ref "R190") (pin "2") (pinfunction "2_2") (pintype "passive"))
    )
    (net (code "239") (name "Net-(LED64-GREEN_A)") (class "Default")
      (node (ref "LED64") (pin "1") (pinfunction "GREEN_A_1") (pintype "bidirectional"))
      (node (ref "R191") (pin "2") (pinfunction "2_2") (pintype "passive"))
    )
    (net (code "240") (name "Net-(LED64-RED_A)") (class "Default")
      (node (ref "LED64") (pin "2") (pinfunction "RED_A_2") (pintype "bidirectional"))
      (node (ref "R192") (pin "2") (pinfunction "2_2") (pintype "passive"))
    )
    (net (code "241") (name "Net-(Q1-B)") (class "Default")
      (node (ref "Q1") (pin "2") (pinfunction "B_2") (pintype "passive"))
      (node (ref "R193") (pin "2") (pinfunction "2_2") (pintype "passive"))
    )
    (net (code "242") (name "Net-(Q2-B)") (class "Default")
      (node (ref "Q2") (pin "2") (pinfunction "B_2") (pintype "passive"))
      (node (ref "R194") (pin "2") (pinfunction "2_2") (pintype "passive"))
    )
    (net (code "243") (name "Net-(Q3-B)") (class "Default")
      (node (ref "Q3") (pin "2") (pinfunction "B_2") (pintype "passive"))
      (node (ref "R195") (pin "2") (pinfunction "2_2") (pintype "passive"))
    )
    (net (code "244") (name "Net-(Q4-B)") (class "Default")
      (node (ref "Q4") (pin "2") (pinfunction "B_2") (pintype "passive"))
      (node (ref "R196") (pin "2") (pinfunction "2_2") (pintype "passive"))
    )
    (net (code "245") (name "Net-(Q5-B)") (class "Default")
      (node (ref "Q5") (pin "2") (pinfunction "B_2") (pintype "passive"))
      (node (ref "R197") (pin "2") (pinfunction "2_2") (pintype "passive"))
    )
    (net (code "246") (name "Net-(Q6-B)") (class "Default")
      (node (ref "Q6") (pin "2") (pinfunction "B_2") (pintype "passive"))
      (node (ref "R198") (pin "2") (pinfunction "2_2") (pintype "passive"))
    )
    (net (code "247") (name "Net-(Q7-B)") (class "Default")
      (node (ref "Q7") (pin "2") (pinfunction "B_2") (pintype "passive"))
      (node (ref "R199") (pin "2") (pinfunction "2_2") (pintype "passive"))
    )
    (net (code "248") (name "Net-(Q8-B)") (class "Default")
      (node (ref "Q8") (pin "2") (pinfunction "B_2") (pintype "passive"))
      (node (ref "R200") (pin "2") (pinfunction "2_2") (pintype "passive"))
    )
    (net (code "249") (name "unconnected-(IC3A-QH*-Pad9)") (class "Default")
      (node (ref "IC3") (pin "9") (pinfunction "QH*_9") (pintype "tri_state"))
    )
    (net (code "250") (name "unconnected-(IC4A-QH*-Pad9)") (class "Default")
      (node (ref "IC4") (pin "9") (pinfunction "QH*_9") (pintype "tri_state"))
    )
  )
)
